# EEZ_DIB_AFE3_r1B1.net
KiCad netlist of a schematic drawn in EAGLE
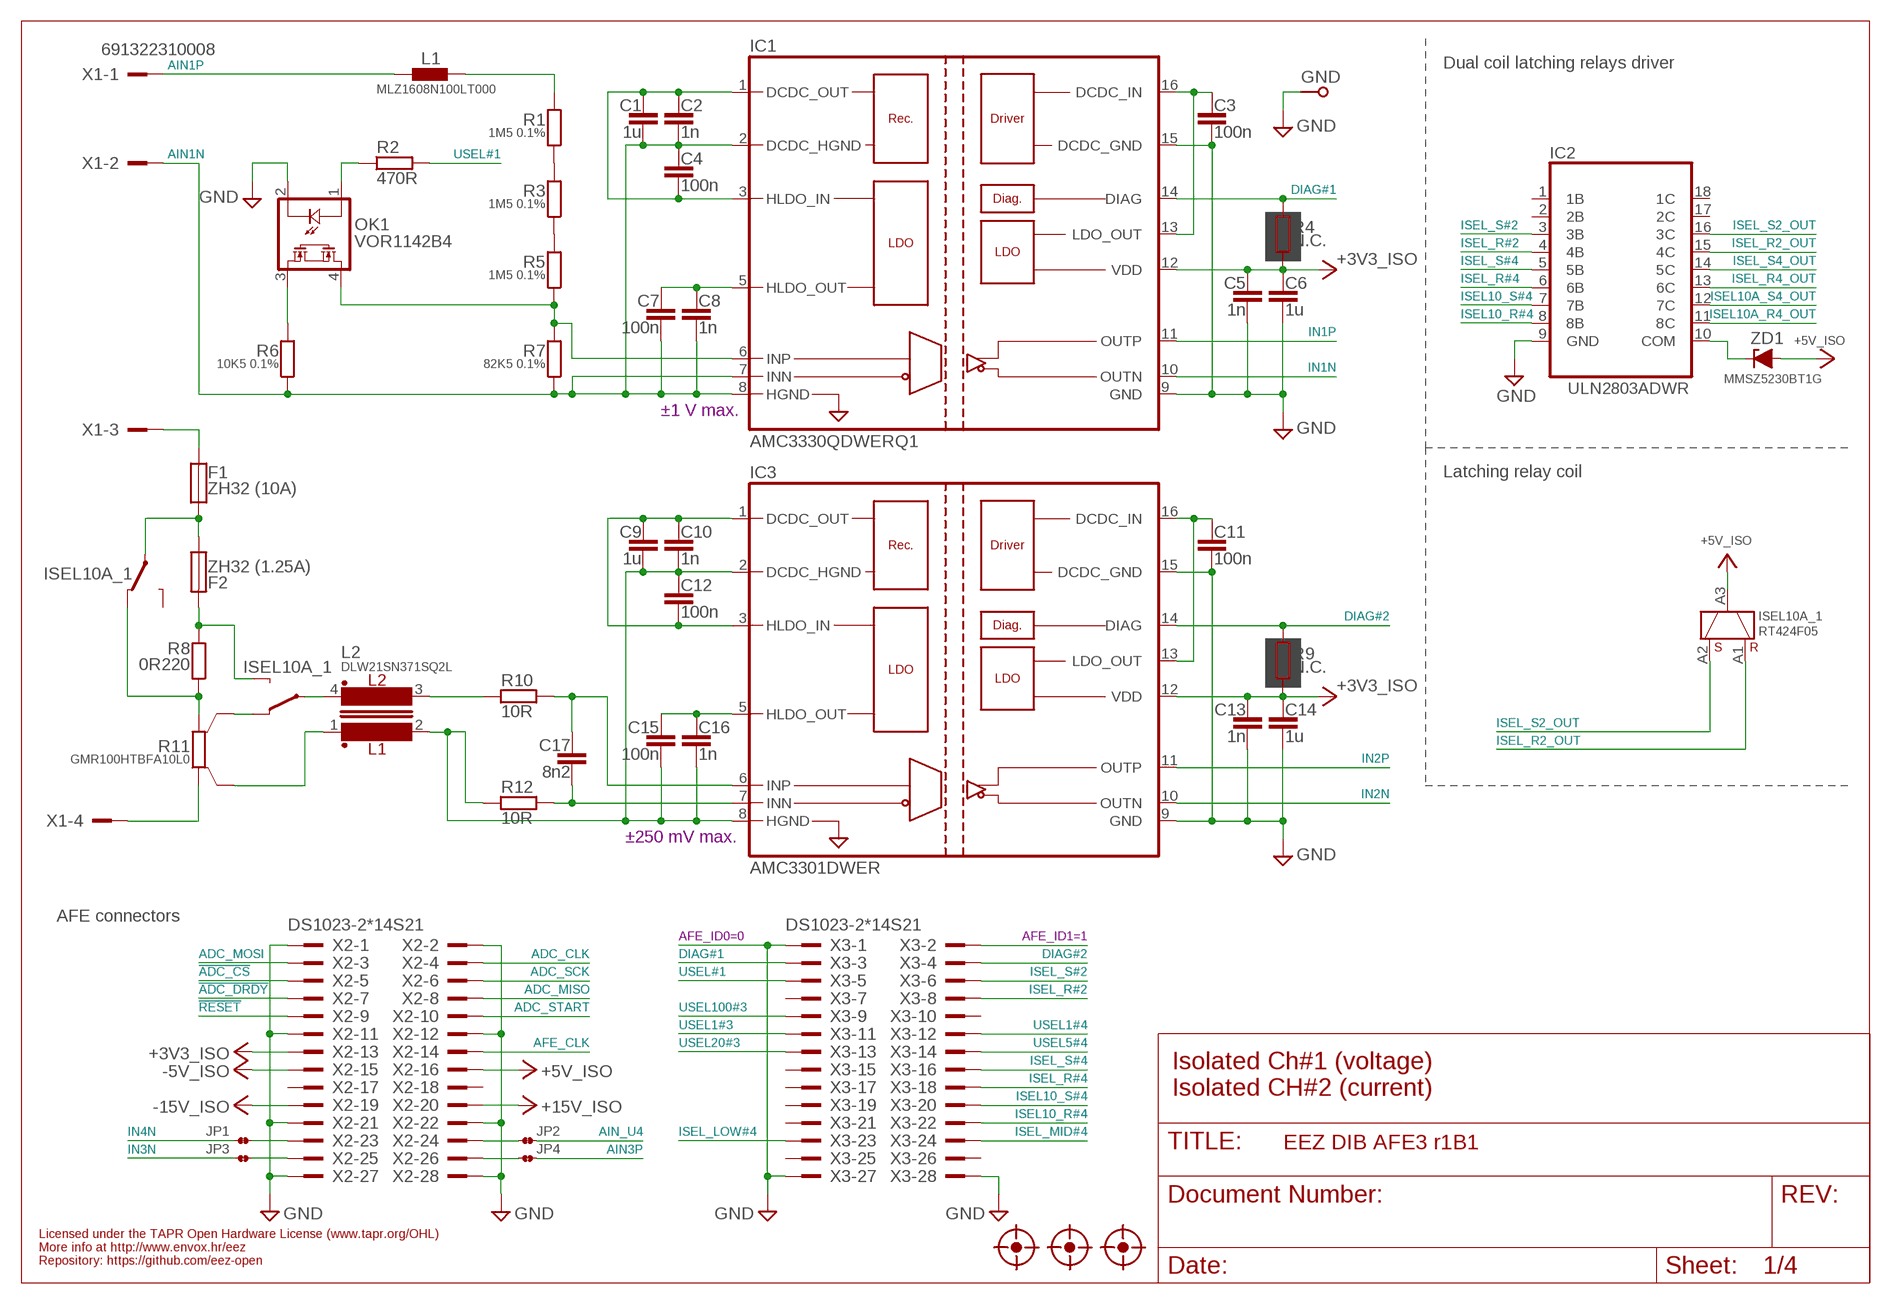
[diagram p0: schematic, sheet 1]
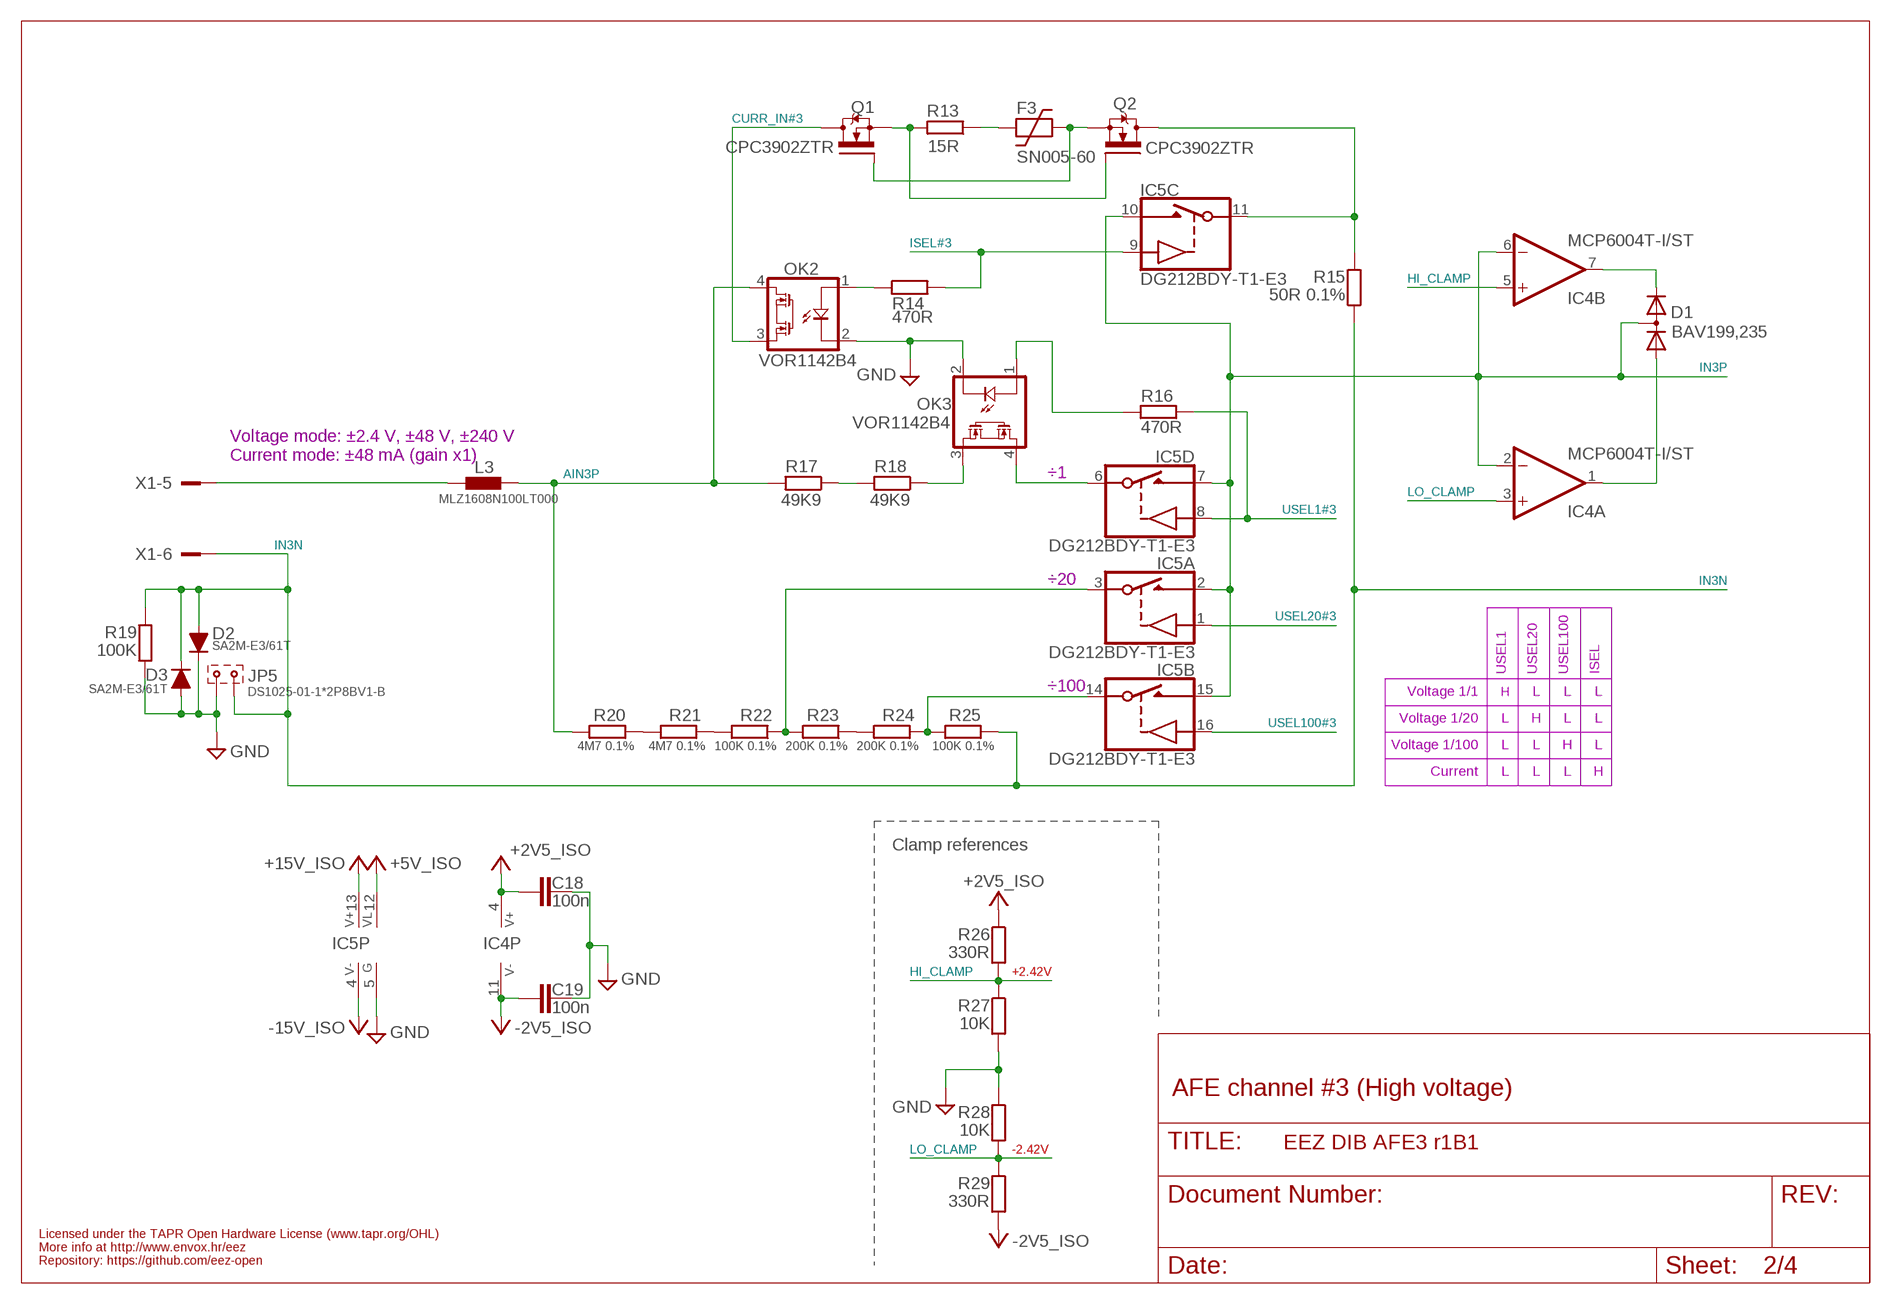
[diagram p1: schematic, sheet 2]
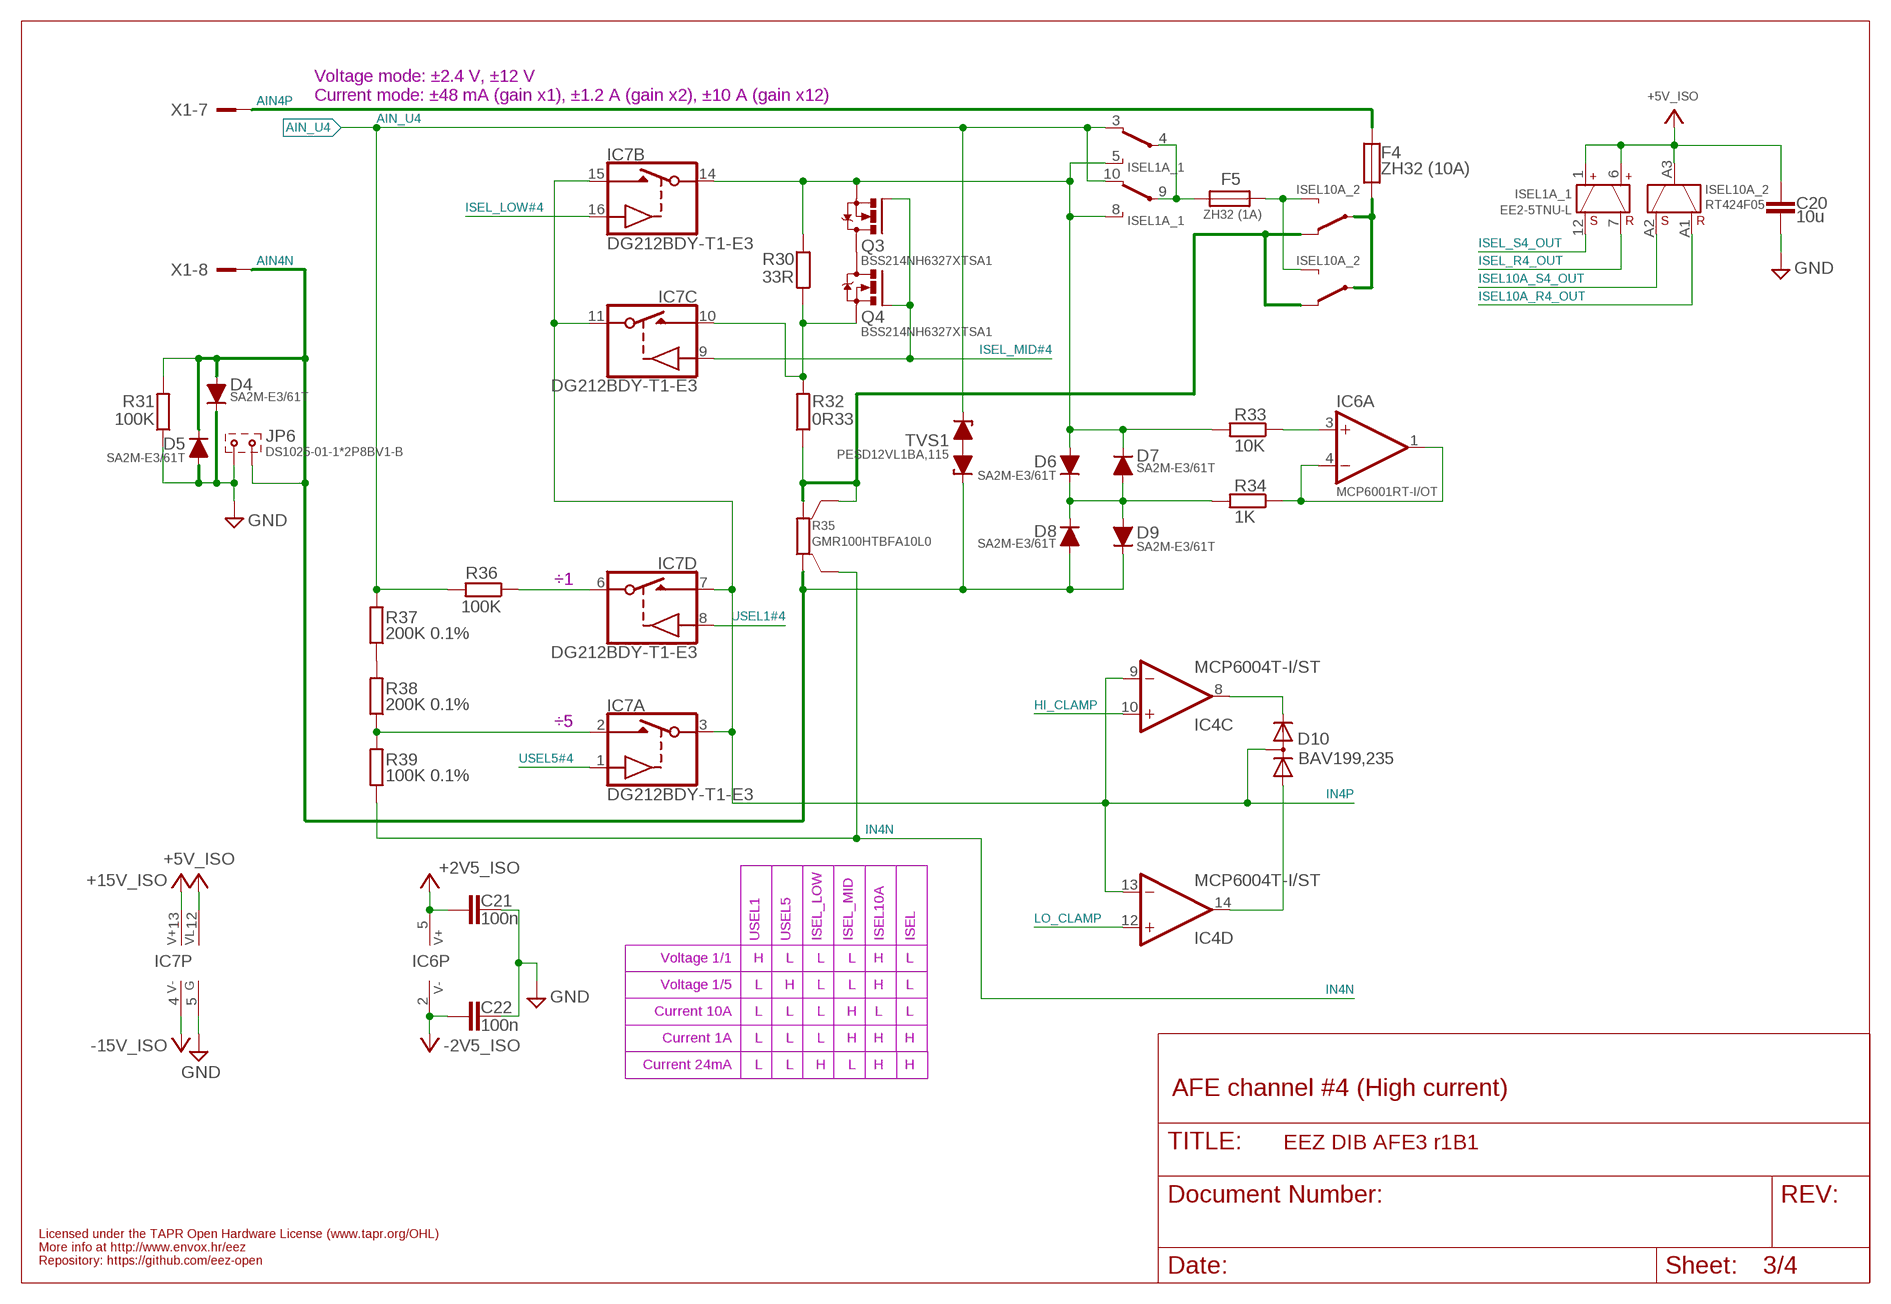
[diagram p2: schematic, sheet 3]
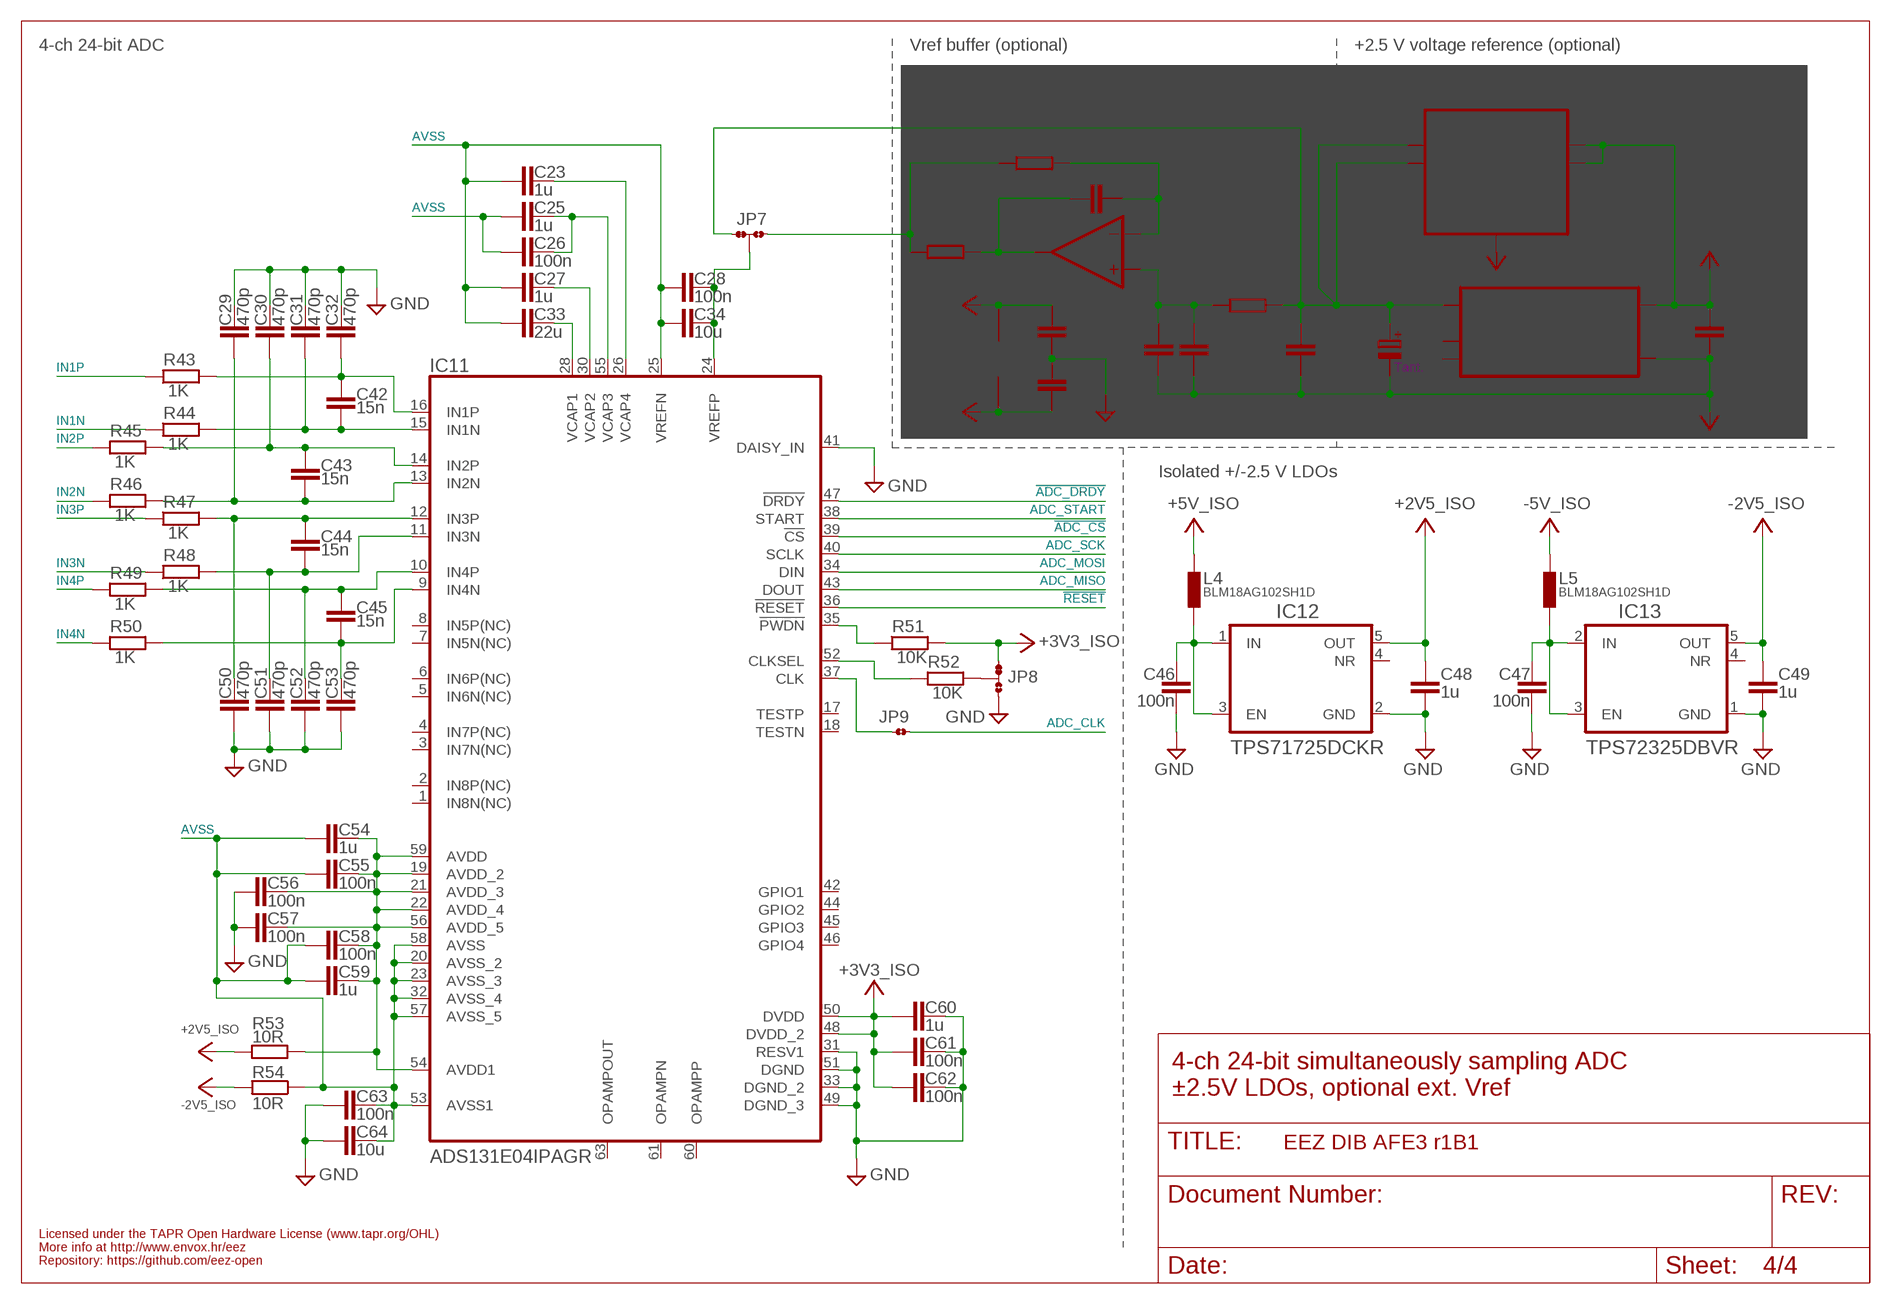
[diagram p3: schematic, sheet 4]

(export (version "E")
  (design (tool "Eeschema 10.0.6"))
  (components
    (comp (ref "C20")
      (value "10u")
      (footprint "eagle-import:C1206")
      (libsource (lib "eagle-import") (part "C-EUC1206"))
    )
    (comp (ref "C21")
      (value "100n")
      (footprint "eagle-import:C0603")
      (libsource (lib "eagle-import") (part "C-EUC0603"))
    )
    (comp (ref "C22")
      (value "100n")
      (footprint "eagle-import:C0603")
      (libsource (lib "eagle-import") (part "C-EUC0603"))
    )
    (comp (ref "D4")
      (value "SA2M-E3/61T")
      (footprint "eagle-import:SMA_NARROW")
      (libsource (lib "eagle-import") (part "DIODE_SMA-NARROW"))
    )
    (comp (ref "D5")
      (value "SA2M-E3/61T")
      (footprint "eagle-import:SMA_NARROW")
      (libsource (lib "eagle-import") (part "DIODE_SMA-NARROW"))
    )
    (comp (ref "D6")
      (value "SA2M-E3/61T")
      (footprint "eagle-import:SMA_NARROW")
      (libsource (lib "eagle-import") (part "DIODE_SMA-NARROW"))
    )
    (comp (ref "D7")
      (value "SA2M-E3/61T")
      (footprint "eagle-import:SMA_NARROW")
      (libsource (lib "eagle-import") (part "DIODE_SMA-NARROW"))
    )
    (comp (ref "D8")
      (value "SA2M-E3/61T")
      (footprint "eagle-import:SMA_NARROW")
      (libsource (lib "eagle-import") (part "DIODE_SMA-NARROW"))
    )
    (comp (ref "D9")
      (value "SA2M-E3/61T")
      (footprint "eagle-import:SMA_NARROW")
      (libsource (lib "eagle-import") (part "DIODE_SMA-NARROW"))
    )
    (comp (ref "D10")
      (value "BAV199,235")
      (footprint "eagle-import:SOT23")
      (libsource (lib "eagle-import") (part "BAV199"))
    )
    (comp (ref "F4")
      (value "ZH32 (10A)")
      (footprint "eagle-import:ZH32")
      (libsource (lib "eagle-import") (part "ZH32"))
    )
    (comp (ref "F5")
      (value "ZH32 (1A)")
      (footprint "eagle-import:ZH32")
      (libsource (lib "eagle-import") (part "ZH32"))
    )
    (comp (ref "IC4")
      (value "MCP6004T-I/ST")
      (footprint "eagle-import:PW(R-PDSO-G14)")
      (libsource (lib "eagle-import") (part "OPA4197PW"))
    )
    (comp (ref "IC6")
      (value "MCP6001RT-I/OT")
      (footprint "eagle-import:DBV5")
      (libsource (lib "eagle-import") (part "OPA376AIDBVR"))
    )
    (comp (ref "IC7")
      (value "DG212BDY-T1-E3")
      (footprint "eagle-import:SO16")
      (libsource (lib "eagle-import") (part "DG212BDY-T1-E3"))
    )
    (comp (ref "ISEL1A_1")
      (value "EE2-5TNU-L")
      (footprint "eagle-import:G6SK-2F")
      (libsource (lib "eagle-import") (part "G6SK-2F"))
    )
    (comp (ref "ISEL10A_2")
      (value "RT424F05")
      (footprint "eagle-import:RT424FXX")
      (libsource (lib "eagle-import") (part "RT424FXX"))
    )
    (comp (ref "JP6")
      (value "DS1025-01-1*2P8BV1-B")
      (footprint "eagle-import:2MM-2")
      (libsource (lib "eagle-import") (part "JUMPER-2PIN-2MM"))
    )
    (comp (ref "Q3")
      (value "BSS214NH6327XTSA1")
      (footprint "eagle-import:SOT103P240X110-3N")
      (fields
        (field (name "MPN") "2N7002-7-F")
        (field (name "MPN_1") "2N7002-7-F")
        (field (name "OC_FARNELL") "1713823")
        (field (name "OC_NEWARK") "25R5679")
        (field (name "PACKAGE") "SOT-23-3")
        (field (name "SUPPLIER") "DIODES INC.")
      )
      (libsource (lib "eagle-import") (part "2N7002"))
    )
    (comp (ref "Q4")
      (value "BSS214NH6327XTSA1")
      (footprint "eagle-import:SOT103P240X110-3N")
      (fields (field (name "MPN") "2N7002-7-F"))
      (libsource (lib "eagle-import") (part "2N7002"))
    )
    (comp (ref "R30")
      (value "33R")
      (footprint "eagle-import:R1206")
      (libsource (lib "eagle-import") (part "R-EU_R1206"))
    )
    (comp (ref "R31")
      (value "100K")
      (footprint "eagle-import:R1206")
      (libsource (lib "eagle-import") (part "R-EU_R1206"))
    )
    (comp (ref "R32")
      (value "0R33")
      (footprint "eagle-import:R1210")
      (libsource (lib "eagle-import") (part "R-EU_R1210"))
    )
    (comp (ref "R33")
      (value "10K")
      (footprint "eagle-import:R0805")
      (libsource (lib "eagle-import") (part "R-EU_R0805"))
    )
    (comp (ref "R34")
      (value "1K")
      (footprint "eagle-import:R0805")
      (libsource (lib "eagle-import") (part "R-EU_R0805"))
    )
    (comp (ref "R35")
      (value "GMR100HTBFA10L0")
      (footprint "eagle-import:R_2512-4WIRE")
      (libsource (lib "eagle-import") (part "R-EU_4WIRE2512"))
    )
    (comp (ref "R36")
      (value "100K")
      (footprint "eagle-import:R1206")
      (libsource (lib "eagle-import") (part "R-EU_R1206"))
    )
    (comp (ref "R37")
      (value "200K 0.1%")
      (footprint "eagle-import:R1206")
      (libsource (lib "eagle-import") (part "R-EU_R1206"))
    )
    (comp (ref "R38")
      (value "200K 0.1%")
      (footprint "eagle-import:R1206")
      (libsource (lib "eagle-import") (part "R-EU_R1206"))
    )
    (comp (ref "R39")
      (value "100K 0.1%")
      (footprint "eagle-import:R1206")
      (libsource (lib "eagle-import") (part "R-EU_R1206"))
    )
    (comp (ref "TVS1")
      (value "PESD12VL1BA,115")
      (footprint "eagle-import:SOD323-BIDIR")
      (libsource (lib "eagle-import") (part "PESDXL1BA"))
    )
    (comp (ref "X1")
      (value "691322310008")
      (footprint "eagle-import:691322310008")
      (libsource (lib "eagle-import") (part "691322310008"))
    )
    (comp (ref "C1")
      (value "1u")
      (footprint "eagle-import:C0603")
      (libsource (lib "eagle-import") (part "C-EUC0603"))
    )
    (comp (ref "C2")
      (value "1n")
      (footprint "eagle-import:C0603")
      (libsource (lib "eagle-import") (part "C-EUC0603"))
    )
    (comp (ref "C3")
      (value "100n")
      (footprint "eagle-import:C0603")
      (libsource (lib "eagle-import") (part "C-EUC0603"))
    )
    (comp (ref "C4")
      (value "100n")
      (footprint "eagle-import:C0603")
      (libsource (lib "eagle-import") (part "C-EUC0603"))
    )
    (comp (ref "C5")
      (value "1n")
      (footprint "eagle-import:C1206")
      (libsource (lib "eagle-import") (part "C-EUC1206"))
    )
    (comp (ref "C6")
      (value "1u")
      (footprint "eagle-import:C1206")
      (libsource (lib "eagle-import") (part "C-EUC1206"))
    )
    (comp (ref "C7")
      (value "100n")
      (footprint "eagle-import:C1206")
      (libsource (lib "eagle-import") (part "C-EUC1206"))
    )
    (comp (ref "C8")
      (value "1n")
      (footprint "eagle-import:C1206")
      (libsource (lib "eagle-import") (part "C-EUC1206"))
    )
    (comp (ref "C9")
      (value "1u")
      (footprint "eagle-import:C0603")
      (libsource (lib "eagle-import") (part "C-EUC0603"))
    )
    (comp (ref "C10")
      (value "1n")
      (footprint "eagle-import:C0603")
      (libsource (lib "eagle-import") (part "C-EUC0603"))
    )
    (comp (ref "C11")
      (value "100n")
      (footprint "eagle-import:C0603")
      (libsource (lib "eagle-import") (part "C-EUC0603"))
    )
    (comp (ref "C12")
      (value "100n")
      (footprint "eagle-import:C0603")
      (libsource (lib "eagle-import") (part "C-EUC0603"))
    )
    (comp (ref "C13")
      (value "1n")
      (footprint "eagle-import:C1206")
      (libsource (lib "eagle-import") (part "C-EUC1206"))
    )
    (comp (ref "C14")
      (value "1u")
      (footprint "eagle-import:C1206")
      (libsource (lib "eagle-import") (part "C-EUC1206"))
    )
    (comp (ref "C15")
      (value "100n")
      (footprint "eagle-import:C1206")
      (libsource (lib "eagle-import") (part "C-EUC1206"))
    )
    (comp (ref "C16")
      (value "1n")
      (footprint "eagle-import:C1206")
      (libsource (lib "eagle-import") (part "C-EUC1206"))
    )
    (comp (ref "C17")
      (value "8n2")
      (footprint "eagle-import:C0603")
      (libsource (lib "eagle-import") (part "C-EUC0603"))
    )
    (comp (ref "F1")
      (value "ZH32 (10A)")
      (footprint "eagle-import:ZH32")
      (libsource (lib "eagle-import") (part "ZH32"))
    )
    (comp (ref "F2")
      (value "ZH32 (1.25A)")
      (footprint "eagle-import:ZH32")
      (libsource (lib "eagle-import") (part "ZH32"))
    )
    (comp (ref "FM1")
      (value "FIDUCIAL_2")
      (footprint "eagle-import:FIDUCIAL_DUAL")
      (libsource (lib "eagle-import") (part "FIDUCIAL_2"))
    )
    (comp (ref "FM2")
      (value "FIDUCIAL_2")
      (footprint "eagle-import:FIDUCIAL_DUAL")
      (libsource (lib "eagle-import") (part "FIDUCIAL_2"))
    )
    (comp (ref "FM3")
      (value "FIDUCIAL_2")
      (footprint "eagle-import:FIDUCIAL_DUAL")
      (libsource (lib "eagle-import") (part "FIDUCIAL_2"))
    )
    (comp (ref "GND")
      (value "PCB_TEST_TABSHIELD")
      (footprint "eagle-import:PCB_SHIELD_TAB")
      (libsource (lib "eagle-import") (part "PCB_TEST_TABSHIELD"))
    )
    (comp (ref "IC1")
      (value "AMC3330QDWERQ1")
      (footprint "eagle-import:DW16")
      (libsource (lib "eagle-import") (part "AMC3301DWER"))
    )
    (comp (ref "IC2")
      (value "ULN2803ADWR")
      (footprint "eagle-import:DW18_TEX-M")
      (libsource (lib "eagle-import") (part "ULN2803ADWR"))
    )
    (comp (ref "IC3")
      (value "AMC3301DWER")
      (footprint "eagle-import:DW16")
      (libsource (lib "eagle-import") (part "AMC3301DWER"))
    )
    (comp (ref "ISEL10A_1")
      (value "RT424F05")
      (footprint "eagle-import:RT424FXX")
      (libsource (lib "eagle-import") (part "RT424FXX"))
    )
    (comp (ref "JP1")
      (value "JP2-NOCUT-0805")
      (footprint "eagle-import:JP2-0805-NOCUT")
      (libsource (lib "eagle-import") (part "JP2-NOCUT-0805"))
    )
    (comp (ref "JP2")
      (value "JP2-NOCUT-0805")
      (footprint "eagle-import:JP2-0805-NOCUT")
      (libsource (lib "eagle-import") (part "JP2-NOCUT-0805"))
    )
    (comp (ref "JP3")
      (value "JP2-NOCUT-0805")
      (footprint "eagle-import:JP2-0805-NOCUT")
      (libsource (lib "eagle-import") (part "JP2-NOCUT-0805"))
    )
    (comp (ref "JP4")
      (value "JP2-NOCUT-0805")
      (footprint "eagle-import:JP2-0805-NOCUT")
      (libsource (lib "eagle-import") (part "JP2-NOCUT-0805"))
    )
    (comp (ref "L1")
      (value "MLZ1608N100LT000")
      (footprint "eagle-import:BEAD0603")
      (libsource (lib "eagle-import") (part "FERRITE_BEAD0603"))
    )
    (comp (ref "L2")
      (value "DLW21SN371SQ2L")
      (footprint "eagle-import:MURATA_DLW21S")
      (libsource (lib "eagle-import") (part "DLW21S"))
    )
    (comp (ref "OK1")
      (value "VOR1142B4")
      (footprint "eagle-import:DIL4-SMD")
      (libsource (lib "eagle-import") (part "VOR1142B4"))
    )
    (comp (ref "R1")
      (value "1M5 0.1%")
      (footprint "eagle-import:R1206")
      (libsource (lib "eagle-import") (part "R-EU_R1206"))
    )
    (comp (ref "R2")
      (value "470R")
      (footprint "eagle-import:R0805")
      (libsource (lib "eagle-import") (part "R-EU_R0805"))
    )
    (comp (ref "R3")
      (value "1M5 0.1%")
      (footprint "eagle-import:R1206")
      (libsource (lib "eagle-import") (part "R-EU_R1206"))
    )
    (comp (ref "R4")
      (value "N.C.")
      (footprint "eagle-import:R0805")
      (libsource (lib "eagle-import") (part "R-EU_R0805"))
    )
    (comp (ref "R5")
      (value "1M5 0.1%")
      (footprint "eagle-import:R1206")
      (libsource (lib "eagle-import") (part "R-EU_R1206"))
    )
    (comp (ref "R6")
      (value "10K5 0.1%")
      (footprint "eagle-import:R1206")
      (libsource (lib "eagle-import") (part "R-EU_R1206"))
    )
    (comp (ref "R7")
      (value "82K5 0.1%")
      (footprint "eagle-import:R1206")
      (libsource (lib "eagle-import") (part "R-EU_R1206"))
    )
    (comp (ref "R8")
      (value "0R220")
      (footprint "eagle-import:R1210")
      (libsource (lib "eagle-import") (part "R-EU_R1210"))
    )
    (comp (ref "R9")
      (value "N.C.")
      (footprint "eagle-import:R0805")
      (libsource (lib "eagle-import") (part "R-EU_R0805"))
    )
    (comp (ref "R10")
      (value "10R")
      (footprint "eagle-import:R0805")
      (libsource (lib "eagle-import") (part "R-EU_R0805"))
    )
    (comp (ref "R11")
      (value "GMR100HTBFA10L0")
      (footprint "eagle-import:R_2512-4WIRE")
      (libsource (lib "eagle-import") (part "R-EU_4WIRE2512"))
    )
    (comp (ref "R12")
      (value "10R")
      (footprint "eagle-import:R0805")
      (libsource (lib "eagle-import") (part "R-EU_R0805"))
    )
    (comp (ref "X2")
      (value "DS1023-2*14S21")
      (footprint "eagle-import:TSW-114-07-F-D")
      (libsource (lib "eagle-import") (part "TSW-114-07-F-D"))
    )
    (comp (ref "X3")
      (value "DS1023-2*14S21")
      (footprint "eagle-import:TSW-114-07-F-D")
      (libsource (lib "eagle-import") (part "TSW-114-07-F-D"))
    )
    (comp (ref "ZD1")
      (value "MMSZ5230BT1G")
      (footprint "eagle-import:SOD123")
      (libsource (lib "eagle-import") (part "ZENER-DIODESOD123"))
    )
    (comp (ref "C23")
      (value "1u")
      (footprint "eagle-import:C0805")
      (libsource (lib "eagle-import") (part "C-EUC0805"))
    )
    (comp (ref "C24")
      (value "N.C.")
      (footprint "eagle-import:C0805")
      (libsource (lib "eagle-import") (part "C-EUC0805"))
    )
    (comp (ref "C25")
      (value "1u")
      (footprint "eagle-import:C0805")
      (libsource (lib "eagle-import") (part "C-EUC0805"))
    )
    (comp (ref "C26")
      (value "100n")
      (footprint "eagle-import:C0603")
      (libsource (lib "eagle-import") (part "C-EUC0603"))
    )
    (comp (ref "C27")
      (value "1u")
      (footprint "eagle-import:C0805")
      (libsource (lib "eagle-import") (part "C-EUC0805"))
    )
    (comp (ref "C28")
      (value "100n")
      (footprint "eagle-import:C0603")
      (libsource (lib "eagle-import") (part "C-EUC0603"))
    )
    (comp (ref "C29")
      (value "470p")
      (footprint "eagle-import:C0603")
      (libsource (lib "eagle-import") (part "C-EUC0603"))
    )
    (comp (ref "C30")
      (value "470p")
      (footprint "eagle-import:C0603")
      (libsource (lib "eagle-import") (part "C-EUC0603"))
    )
    (comp (ref "C31")
      (value "470p")
      (footprint "eagle-import:C0603")
      (libsource (lib "eagle-import") (part "C-EUC0603"))
    )
    (comp (ref "C32")
      (value "470p")
      (footprint "eagle-import:C0603")
      (libsource (lib "eagle-import") (part "C-EUC0603"))
    )
    (comp (ref "C33")
      (value "22u")
      (footprint "eagle-import:C1206")
      (libsource (lib "eagle-import") (part "C-EUC1206"))
    )
    (comp (ref "C34")
      (value "10u")
      (footprint "eagle-import:C1206")
      (libsource (lib "eagle-import") (part "C-EUC1206"))
    )
    (comp (ref "C35")
      (value "N.C.")
      (footprint "eagle-import:C0603")
      (libsource (lib "eagle-import") (part "C-EUC0603"))
    )
    (comp (ref "C36")
      (value "N.C.")
      (footprint "eagle-import:C1206")
      (libsource (lib "eagle-import") (part "C-EUC1206"))
    )
    (comp (ref "C37")
      (value "N.C.")
      (footprint "eagle-import:C1206")
      (libsource (lib "eagle-import") (part "C-EUC1206"))
    )
    (comp (ref "C38")
      (value "N.C.")
      (footprint "eagle-import:C1206")
      (libsource (lib "eagle-import") (part "C-EUC1206"))
    )
    (comp (ref "C39")
      (value "N.C.")
      (footprint "eagle-import:C1206")
      (libsource (lib "eagle-import") (part "C-EUC1206"))
    )
    (comp (ref "C40")
      (value "N.C.")
      (footprint "eagle-import:EC1206")
      (libsource (lib "eagle-import") (part "ECAP1206"))
    )
    (comp (ref "C41")
      (value "N.C.")
      (footprint "eagle-import:C0603")
      (libsource (lib "eagle-import") (part "C-EUC0603"))
    )
    (comp (ref "C42")
      (value "15n")
      (footprint "eagle-import:C0603")
      (libsource (lib "eagle-import") (part "C-EUC0603"))
    )
    (comp (ref "C43")
      (value "15n")
      (footprint "eagle-import:C0603")
      (libsource (lib "eagle-import") (part "C-EUC0603"))
    )
    (comp (ref "C44")
      (value "15n")
      (footprint "eagle-import:C0603")
      (libsource (lib "eagle-import") (part "C-EUC0603"))
    )
    (comp (ref "C45")
      (value "15n")
      (footprint "eagle-import:C0603")
      (libsource (lib "eagle-import") (part "C-EUC0603"))
    )
    (comp (ref "C46")
      (value "100n")
      (footprint "eagle-import:C0603")
      (libsource (lib "eagle-import") (part "C-EUC0603"))
    )
    (comp (ref "C47")
      (value "100n")
      (footprint "eagle-import:C0603")
      (libsource (lib "eagle-import") (part "C-EUC0603"))
    )
    (comp (ref "C48")
      (value "1u")
      (footprint "eagle-import:C0805")
      (libsource (lib "eagle-import") (part "C-EUC0805"))
    )
    (comp (ref "C49")
      (value "1u")
      (footprint "eagle-import:C0805")
      (libsource (lib "eagle-import") (part "C-EUC0805"))
    )
    (comp (ref "C50")
      (value "470p")
      (footprint "eagle-import:C0603")
      (libsource (lib "eagle-import") (part "C-EUC0603"))
    )
    (comp (ref "C51")
      (value "470p")
      (footprint "eagle-import:C0603")
      (libsource (lib "eagle-import") (part "C-EUC0603"))
    )
    (comp (ref "C52")
      (value "470p")
      (footprint "eagle-import:C0603")
      (libsource (lib "eagle-import") (part "C-EUC0603"))
    )
    (comp (ref "C53")
      (value "470p")
      (footprint "eagle-import:C0603")
      (libsource (lib "eagle-import") (part "C-EUC0603"))
    )
    (comp (ref "C54")
      (value "1u")
      (footprint "eagle-import:C0805")
      (libsource (lib "eagle-import") (part "C-EUC0805"))
    )
    (comp (ref "C55")
      (value "100n")
      (footprint "eagle-import:C0603")
      (libsource (lib "eagle-import") (part "C-EUC0603"))
    )
    (comp (ref "C56")
      (value "100n")
      (footprint "eagle-import:C0603")
      (libsource (lib "eagle-import") (part "C-EUC0603"))
    )
    (comp (ref "C57")
      (value "100n")
      (footprint "eagle-import:C0603")
      (libsource (lib "eagle-import") (part "C-EUC0603"))
    )
    (comp (ref "C58")
      (value "100n")
      (footprint "eagle-import:C0603")
      (libsource (lib "eagle-import") (part "C-EUC0603"))
    )
    (comp (ref "C59")
      (value "1u")
      (footprint "eagle-import:C0805")
      (libsource (lib "eagle-import") (part "C-EUC0805"))
    )
    (comp (ref "C60")
      (value "1u")
      (footprint "eagle-import:C0805")
      (libsource (lib "eagle-import") (part "C-EUC0805"))
    )
    (comp (ref "C61")
      (value "100n")
      (footprint "eagle-import:C0603")
      (libsource (lib "eagle-import") (part "C-EUC0603"))
    )
    (comp (ref "C62")
      (value "100n")
      (footprint "eagle-import:C0603")
      (libsource (lib "eagle-import") (part "C-EUC0603"))
    )
    (comp (ref "C63")
      (value "100n")
      (footprint "eagle-import:C0603")
      (libsource (lib "eagle-import") (part "C-EUC0603"))
    )
    (comp (ref "C64")
      (value "10u")
      (footprint "eagle-import:C1206")
      (libsource (lib "eagle-import") (part "C-EUC1206"))
    )
    (comp (ref "IC8")
      (value "N.C.")
      (footprint "eagle-import:MSOP-8_MS_LIT")
      (libsource (lib "eagle-import") (part "LTC6655BHMS8"))
    )
    (comp (ref "IC9")
      (value "N.C.")
      (footprint "eagle-import:DBV5")
      (libsource (lib "eagle-import") (part "OPA376AIDBVR"))
    )
    (comp (ref "IC10")
      (value "N.C.")
      (footprint "eagle-import:SOIC127P600X175-8N")
      (libsource (lib "eagle-import") (part "REF50XX"))
    )
    (comp (ref "IC11")
      (value "ADS131E04IPAGR")
      (footprint "eagle-import:PAG64")
      (libsource (lib "eagle-import") (part "ADS131E0XIPAG"))
    )
    (comp (ref "IC12")
      (value "TPS71725DCKR")
      (footprint "eagle-import:DCK5")
      (libsource (lib "eagle-import") (part "TPS71725DCKR"))
    )
    (comp (ref "IC13")
      (value "TPS72325DBVR")
      (footprint "eagle-import:DBV5")
      (libsource (lib "eagle-import") (part "TPS72325DBVR"))
    )
    (comp (ref "JP7")
      (value "JP3-CUT-0805-ROTATED")
      (footprint "eagle-import:JP3-0805-CUT2")
      (libsource (lib "eagle-import") (part "JP3-CUT-0805-ROTATED"))
    )
    (comp (ref "JP8")
      (value "JP3-CUT-0805-ROTATED")
      (footprint "eagle-import:JP3-0805-CUT2")
      (libsource (lib "eagle-import") (part "JP3-CUT-0805-ROTATED"))
    )
    (comp (ref "JP9")
      (value "JP2-CUT-0805")
      (footprint "eagle-import:R_0805")
      (libsource (lib "eagle-import") (part "JP2-CUT-0805"))
    )
    (comp (ref "L4")
      (value "BLM18AG102SH1D")
      (footprint "eagle-import:BEAD0603")
      (libsource (lib "eagle-import") (part "FERRITE_BEAD0603"))
    )
    (comp (ref "L5")
      (value "BLM18AG102SH1D")
      (footprint "eagle-import:BEAD0603")
      (libsource (lib "eagle-import") (part "FERRITE_BEAD0603"))
    )
    (comp (ref "R40")
      (value "N.C.")
      (footprint "eagle-import:R0805")
      (libsource (lib "eagle-import") (part "R-EU_R0805"))
    )
    (comp (ref "R41")
      (value "N.C.")
      (footprint "eagle-import:R0805")
      (libsource (lib "eagle-import") (part "R-EU_R0805"))
    )
    (comp (ref "R42")
      (value "N.C.")
      (footprint "eagle-import:R0805")
      (libsource (lib "eagle-import") (part "R-EU_R0805"))
    )
    (comp (ref "R43")
      (value "1K")
      (footprint "eagle-import:R0805")
      (libsource (lib "eagle-import") (part "R-EU_R0805"))
    )
    (comp (ref "R44")
      (value "1K")
      (footprint "eagle-import:R0805")
      (libsource (lib "eagle-import") (part "R-EU_R0805"))
    )
    (comp (ref "R45")
      (value "1K")
      (footprint "eagle-import:R0805")
      (libsource (lib "eagle-import") (part "R-EU_R0805"))
    )
    (comp (ref "R46")
      (value "1K")
      (footprint "eagle-import:R0805")
      (libsource (lib "eagle-import") (part "R-EU_R0805"))
    )
    (comp (ref "R47")
      (value "1K")
      (footprint "eagle-import:R0805")
      (libsource (lib "eagle-import") (part "R-EU_R0805"))
    )
    (comp (ref "R48")
      (value "1K")
      (footprint "eagle-import:R0805")
      (libsource (lib "eagle-import") (part "R-EU_R0805"))
    )
    (comp (ref "R49")
      (value "1K")
      (footprint "eagle-import:R0805")
      (libsource (lib "eagle-import") (part "R-EU_R0805"))
    )
    (comp (ref "R50")
      (value "1K")
      (footprint "eagle-import:R0805")
      (libsource (lib "eagle-import") (part "R-EU_R0805"))
    )
    (comp (ref "R51")
      (value "10K")
      (footprint "eagle-import:R0805")
      (libsource (lib "eagle-import") (part "R-EU_R0805"))
    )
    (comp (ref "R52")
      (value "10K")
      (footprint "eagle-import:R0805")
      (libsource (lib "eagle-import") (part "R-EU_R0805"))
    )
    (comp (ref "R53")
      (value "10R")
      (footprint "eagle-import:R0805")
      (libsource (lib "eagle-import") (part "R-EU_R0805"))
    )
    (comp (ref "R54")
      (value "10R")
      (footprint "eagle-import:R0805")
      (libsource (lib "eagle-import") (part "R-EU_R0805"))
    )
    (comp (ref "C18")
      (value "100n")
      (footprint "eagle-import:C0603")
      (libsource (lib "eagle-import") (part "C-EUC0603"))
    )
    (comp (ref "C19")
      (value "100n")
      (footprint "eagle-import:C0603")
      (libsource (lib "eagle-import") (part "C-EUC0603"))
    )
    (comp (ref "D1")
      (value "BAV199,235")
      (footprint "eagle-import:SOT23")
      (libsource (lib "eagle-import") (part "BAV199"))
    )
    (comp (ref "D2")
      (value "SA2M-E3/61T")
      (footprint "eagle-import:SMA_NARROW")
      (libsource (lib "eagle-import") (part "DIODE_SMA-NARROW"))
    )
    (comp (ref "D3")
      (value "SA2M-E3/61T")
      (footprint "eagle-import:SMA_NARROW")
      (libsource (lib "eagle-import") (part "DIODE_SMA-NARROW"))
    )
    (comp (ref "F3")
      (value "SN005-60")
      (footprint "eagle-import:C1206-HV")
      (libsource (lib "eagle-import") (part "FUSE_RESETTABLE2"))
    )
    (comp (ref "IC5")
      (value "DG212BDY-T1-E3")
      (footprint "eagle-import:SO16")
      (libsource (lib "eagle-import") (part "DG212BDY-T1-E3"))
    )
    (comp (ref "JP5")
      (value "DS1025-01-1*2P8BV1-B")
      (footprint "eagle-import:2MM-2")
      (libsource (lib "eagle-import") (part "JUMPER-2PIN-2MM"))
    )
    (comp (ref "L3")
      (value "MLZ1608N100LT000")
      (footprint "eagle-import:BEAD0603")
      (libsource (lib "eagle-import") (part "FERRITE_BEAD0603"))
    )
    (comp (ref "OK2")
      (value "VOR1142B4")
      (footprint "eagle-import:DIL4-SMD")
      (libsource (lib "eagle-import") (part "VOR1142B4"))
    )
    (comp (ref "OK3")
      (value "VOR1142B4")
      (footprint "eagle-import:DIL4-SMD")
      (libsource (lib "eagle-import") (part "VOR1142B4"))
    )
    (comp (ref "Q1")
      (value "CPC3902ZTR")
      (footprint "eagle-import:SOT230P700X180-4N")
      (libsource (lib "eagle-import") (part "BSP129SOT-223"))
    )
    (comp (ref "Q2")
      (value "CPC3902ZTR")
      (footprint "eagle-import:SOT230P700X180-4N")
      (libsource (lib "eagle-import") (part "BSP129SOT-223"))
    )
    (comp (ref "R13")
      (value "15R")
      (footprint "eagle-import:R0805")
      (libsource (lib "eagle-import") (part "R-EU_R0805"))
    )
    (comp (ref "R14")
      (value "470R")
      (footprint "eagle-import:R0805")
      (libsource (lib "eagle-import") (part "R-EU_R0805"))
    )
    (comp (ref "R15")
      (value "50R 0.1%")
      (footprint "eagle-import:R1206")
      (libsource (lib "eagle-import") (part "R-EU_R1206"))
    )
    (comp (ref "R16")
      (value "470R")
      (footprint "eagle-import:R0805")
      (libsource (lib "eagle-import") (part "R-EU_R0805"))
    )
    (comp (ref "R17")
      (value "49K9")
      (footprint "eagle-import:R1206")
      (libsource (lib "eagle-import") (part "R-EU_R1206"))
    )
    (comp (ref "R18")
      (value "49K9")
      (footprint "eagle-import:R1206")
      (libsource (lib "eagle-import") (part "R-EU_R1206"))
    )
    (comp (ref "R19")
      (value "100K")
      (footprint "eagle-import:R1206")
      (libsource (lib "eagle-import") (part "R-EU_R1206"))
    )
    (comp (ref "R20")
      (value "4M7 0.1%")
      (footprint "eagle-import:R1206")
      (libsource (lib "eagle-import") (part "R-EU_R1206"))
    )
    (comp (ref "R21")
      (value "4M7 0.1%")
      (footprint "eagle-import:R1206")
      (libsource (lib "eagle-import") (part "R-EU_R1206"))
    )
    (comp (ref "R22")
      (value "100K 0.1%")
      (footprint "eagle-import:R1206")
      (libsource (lib "eagle-import") (part "R-EU_R1206"))
    )
    (comp (ref "R23")
      (value "200K 0.1%")
      (footprint "eagle-import:R1206")
      (libsource (lib "eagle-import") (part "R-EU_R1206"))
    )
    (comp (ref "R24")
      (value "200K 0.1%")
      (footprint "eagle-import:R1206")
      (libsource (lib "eagle-import") (part "R-EU_R1206"))
    )
    (comp (ref "R25")
      (value "100K 0.1%")
      (footprint "eagle-import:R1206")
      (libsource (lib "eagle-import") (part "R-EU_R1206"))
    )
    (comp (ref "R26")
      (value "330R")
      (footprint "eagle-import:R0805")
      (libsource (lib "eagle-import") (part "R-EU_R0805"))
    )
    (comp (ref "R27")
      (value "10K")
      (footprint "eagle-import:R0805")
      (libsource (lib "eagle-import") (part "R-EU_R0805"))
    )
    (comp (ref "R28")
      (value "10K")
      (footprint "eagle-import:R0805")
      (libsource (lib "eagle-import") (part "R-EU_R0805"))
    )
    (comp (ref "R29")
      (value "330R")
      (footprint "eagle-import:R0805")
      (libsource (lib "eagle-import") (part "R-EU_R0805"))
    )
  )
  (nets
    (net (code "1") (name "+2V5_ISO") (class "Default")
      (node (ref "C18") (pin "2") (pinfunction "2_2") (pintype "passive"))
      (node (ref "C21") (pin "2") (pinfunction "2_2") (pintype "passive"))
      (node (ref "C48") (pin "2") (pinfunction "2_2") (pintype "passive"))
      (node (ref "IC12") (pin "5") (pinfunction "OUT_5") (pintype "passive"))
      (node (ref "IC4") (pin "4") (pinfunction "V+_4") (pintype "power_in"))
      (node (ref "IC6") (pin "5") (pinfunction "V+_5") (pintype "power_in"))
      (node (ref "R26") (pin "1") (pinfunction "1_1") (pintype "passive"))
      (node (ref "R53") (pin "1") (pinfunction "1_1") (pintype "passive"))
    )
    (net (code "2") (name "+3V3_ISO") (class "Default")
      (node (ref "C13") (pin "1") (pinfunction "1_1") (pintype "passive"))
      (node (ref "C14") (pin "1") (pinfunction "1_1") (pintype "passive"))
      (node (ref "C5") (pin "1") (pinfunction "1_1") (pintype "passive"))
      (node (ref "C6") (pin "1") (pinfunction "1_1") (pintype "passive"))
      (node (ref "C60") (pin "1") (pinfunction "1_1") (pintype "passive"))
      (node (ref "C61") (pin "2") (pinfunction "2_2") (pintype "passive"))
      (node (ref "C62") (pin "2") (pinfunction "2_2") (pintype "passive"))
      (node (ref "IC1") (pin "12") (pinfunction "VDD_12") (pintype "passive"))
      (node (ref "IC11") (pin "48") (pinfunction "DVDD_2_48") (pintype "power_in"))
      (node (ref "IC11") (pin "50") (pinfunction "DVDD_50") (pintype "power_in"))
      (node (ref "IC3") (pin "12") (pinfunction "VDD_12") (pintype "passive"))
      (node (ref "JP8") (pin "NC") (pinfunction "NC_NC") (pintype "passive"))
      (node (ref "R4") (pin "2") (pinfunction "2_2") (pintype "passive"))
      (node (ref "R51") (pin "2") (pinfunction "2_2") (pintype "passive"))
      (node (ref "R9") (pin "2") (pinfunction "2_2") (pintype "passive"))
      (node (ref "X2") (pin "13") (pinfunction "1_13") (pintype "passive"))
    )
    (net (code "3") (name "+5V_ISO") (class "Default")
      (node (ref "C20") (pin "1") (pinfunction "1_1") (pintype "passive"))
      (node (ref "C35") (pin "1") (pinfunction "1_1") (pintype "passive"))
      (node (ref "C36") (pin "1") (pinfunction "1_1") (pintype "passive"))
      (node (ref "IC10") (pin "2") (pinfunction "VIN_2") (pintype "passive"))
      (node (ref "IC5") (pin "12") (pinfunction "VL_12") (pintype "power_in"))
      (node (ref "IC7") (pin "12") (pinfunction "VL_12") (pintype "power_in"))
      (node (ref "IC8") (pin "1") (pinfunction "~{SHDN}_1") (pintype "input"))
      (node (ref "IC8") (pin "2") (pinfunction "VIN_2") (pintype "input"))
      (node (ref "IC9") (pin "5") (pinfunction "V+_5") (pintype "power_in"))
      (node (ref "ISEL10A_1") (pin "A3") (pinfunction "COM_A3") (pintype "passive"))
      (node (ref "ISEL10A_2") (pin "A3") (pinfunction "COM_A3") (pintype "passive"))
      (node (ref "ISEL1A_1") (pin "1") (pinfunction "S+_1") (pintype "passive"))
      (node (ref "ISEL1A_1") (pin "6") (pinfunction "R+_6") (pintype "passive"))
      (node (ref "L4") (pin "P$2") (pinfunction "2_P$2") (pintype "passive"))
      (node (ref "X2") (pin "16") (pinfunction "1_16") (pintype "passive"))
      (node (ref "ZD1") (pin "A") (pinfunction "A_A") (pintype "passive"))
    )
    (net (code "4") (name "+15V_ISO") (class "Default")
      (node (ref "IC5") (pin "13") (pinfunction "V+_13") (pintype "power_in"))
      (node (ref "IC7") (pin "13") (pinfunction "V+_13") (pintype "power_in"))
      (node (ref "X2") (pin "20") (pinfunction "1_20") (pintype "passive"))
    )
    (net (code "5") (name "-2V5_ISO") (class "Default")
      (node (ref "C19") (pin "2") (pinfunction "2_2") (pintype "passive"))
      (node (ref "C22") (pin "2") (pinfunction "2_2") (pintype "passive"))
      (node (ref "C36") (pin "2") (pinfunction "2_2") (pintype "passive"))
      (node (ref "C37") (pin "2") (pinfunction "2_2") (pintype "passive"))
      (node (ref "C38") (pin "2") (pinfunction "2_2") (pintype "passive"))
      (node (ref "C39") (pin "2") (pinfunction "2_2") (pintype "passive"))
      (node (ref "C40") (pin "-") (pinfunction "-_-") (pintype "passive"))
      (node (ref "C49") (pin "2") (pinfunction "2_2") (pintype "passive"))
      (node (ref "IC10") (pin "4") (pinfunction "GND_4") (pintype "passive"))
      (node (ref "IC13") (pin "5") (pinfunction "OUT_5") (pintype "passive"))
      (node (ref "IC4") (pin "11") (pinfunction "V-_11") (pintype "power_in"))
      (node (ref "IC6") (pin "2") (pinfunction "V-_2") (pintype "power_in"))
      (node (ref "IC8") (pin "3") (pinfunction "GND_3") (pintype "power_in"))
      (node (ref "IC8") (pin "4") (pinfunction "GND_4") (pintype "power_in"))
      (node (ref "IC8") (pin "5") (pinfunction "GND_5") (pintype "power_in"))
      (node (ref "IC8") (pin "8") (pinfunction "GND_8") (pintype "power_in"))
      (node (ref "R29") (pin "2") (pinfunction "2_2") (pintype "passive"))
      (node (ref "R54") (pin "2") (pinfunction "2_2") (pintype "passive"))
    )
    (net (code "6") (name "-5V_ISO") (class "Default")
      (node (ref "C41") (pin "2") (pinfunction "2_2") (pintype "passive"))
      (node (ref "IC9") (pin "2") (pinfunction "V-_2") (pintype "power_in"))
      (node (ref "L5") (pin "P$2") (pinfunction "2_P$2") (pintype "passive"))
      (node (ref "X2") (pin "15") (pinfunction "1_15") (pintype "passive"))
    )
    (net (code "7") (name "-15V_ISO") (class "Default")
      (node (ref "IC5") (pin "4") (pinfunction "V-_4") (pintype "power_in"))
      (node (ref "IC7") (pin "4") (pinfunction "V-_4") (pintype "power_in"))
      (node (ref "X2") (pin "19") (pinfunction "1_19") (pintype "passive"))
    )
    (net (code "8") (name "ADC_CLK") (class "Default")
      (node (ref "JP9") (pin "1") (pinfunction "1_1") (pintype "passive"))
      (node (ref "X2") (pin "4") (pinfunction "1_4") (pintype "passive"))
    )
    (net (code "9") (name "ADC_MISO") (class "Default")
      (node (ref "IC11") (pin "43") (pinfunction "DOUT_43") (pintype "output"))
      (node (ref "X2") (pin "8") (pinfunction "1_8") (pintype "passive"))
    )
    (net (code "10") (name "ADC_MOSI") (class "Default")
      (node (ref "IC11") (pin "34") (pinfunction "DIN_34") (pintype "input"))
      (node (ref "X2") (pin "3") (pinfunction "1_3") (pintype "passive"))
    )
    (net (code "11") (name "ADC_SCK") (class "Default")
      (node (ref "IC11") (pin "40") (pinfunction "SCLK_40") (pintype "input"))
      (node (ref "X2") (pin "6") (pinfunction "1_6") (pintype "passive"))
    )
    (net (code "12") (name "ADC_START") (class "Default")
      (node (ref "IC11") (pin "38") (pinfunction "START_38") (pintype "input"))
      (node (ref "X2") (pin "10") (pinfunction "1_10") (pintype "passive"))
    )
    (net (code "13") (name "AFE_CLK") (class "Default")
      (node (ref "X2") (pin "14") (pinfunction "1_14") (pintype "passive"))
    )
    (net (code "14") (name "AIN1N") (class "Default")
      (node (ref "C1") (pin "2") (pinfunction "2_2") (pintype "passive"))
      (node (ref "C2") (pin "2") (pinfunction "2_2") (pintype "passive"))
      (node (ref "C4") (pin "1") (pinfunction "1_1") (pintype "passive"))
      (node (ref "C7") (pin "2") (pinfunction "2_2") (pintype "passive"))
      (node (ref "C8") (pin "2") (pinfunction "2_2") (pintype "passive"))
      (node (ref "IC1") (pin "2") (pinfunction "DCDC_HGND_2") (pintype "passive"))
      (node (ref "IC1") (pin "7") (pinfunction "INN_7") (pintype "input"))
      (node (ref "IC1") (pin "8") (pinfunction "HGND_8") (pintype "passive"))
      (node (ref "R6") (pin "1") (pinfunction "1_1") (pintype "passive"))
      (node (ref "R7") (pin "1") (pinfunction "1_1") (pintype "passive"))
      (node (ref "X1") (pin "2") (pinfunction "1_2") (pintype "passive"))
    )
    (net (code "15") (name "AIN1P") (class "Default")
      (node (ref "L1") (pin "P$2") (pinfunction "2_P$2") (pintype "passive"))
      (node (ref "X1") (pin "1") (pinfunction "1_1") (pintype "passive"))
    )
    (net (code "16") (name "AIN3P") (class "Default")
      (node (ref "JP4") (pin "2") (pinfunction "2_2") (pintype "passive"))
      (node (ref "L3") (pin "P$1") (pinfunction "1_P$1") (pintype "passive"))
      (node (ref "OK2") (pin "4") (pinfunction "S1_4") (pintype "passive"))
      (node (ref "R17") (pin "2") (pinfunction "2_2") (pintype "passive"))
      (node (ref "R20") (pin "2") (pinfunction "2_2") (pintype "passive"))
    )
    (net (code "17") (name "AIN4N") (class "Default")
      (node (ref "D4") (pin "2") (pinfunction "A_2") (pintype "passive"))
      (node (ref "D5") (pin "1") (pinfunction "C_1") (pintype "passive"))
      (node (ref "D8") (pin "2") (pinfunction "A_2") (pintype "passive"))
      (node (ref "D9") (pin "1") (pinfunction "C_1") (pintype "passive"))
      (node (ref "JP6") (pin "1") (pinfunction "1_1") (pintype "passive"))
      (node (ref "R31") (pin "2") (pinfunction "2_2") (pintype "passive"))
      (node (ref "R35") (pin "1") (pinfunction "1_1") (pintype "passive"))
      (node (ref "TVS1") (pin "C1") (pinfunction "1_C1") (pintype "passive"))
      (node (ref "X1") (pin "8") (pinfunction "1_8") (pintype "passive"))
    )
    (net (code "18") (name "AIN4P") (class "Default")
      (node (ref "F4") (pin "2") (pinfunction "2_2") (pintype "passive"))
      (node (ref "X1") (pin "7") (pinfunction "1_7") (pintype "passive"))
    )
    (net (code "19") (name "AIN_U4") (class "Default")
      (node (ref "ISEL1A_1") (pin "10") (pinfunction "NC_10") (pintype "passive"))
      (node (ref "ISEL1A_1") (pin "3") (pinfunction "NC_3") (pintype "passive"))
      (node (ref "JP2") (pin "2") (pinfunction "2_2") (pintype "passive"))
      (node (ref "R36") (pin "2") (pinfunction "2_2") (pintype "passive"))
      (node (ref "R37") (pin "2") (pinfunction "2_2") (pintype "passive"))
      (node (ref "TVS1") (pin "C2") (pinfunction "2_C2") (pintype "passive"))
    )
    (net (code "20") (name "AVSS") (class "Default")
      (node (ref "C23") (pin "1") (pinfunction "1_1") (pintype "passive"))
      (node (ref "C25") (pin "1") (pinfunction "1_1") (pintype "passive"))
      (node (ref "C26") (pin "2") (pinfunction "2_2") (pintype "passive"))
      (node (ref "C27") (pin "1") (pinfunction "1_1") (pintype "passive"))
      (node (ref "C28") (pin "2") (pinfunction "2_2") (pintype "passive"))
      (node (ref "C33") (pin "1") (pinfunction "1_1") (pintype "passive"))
      (node (ref "C34") (pin "2") (pinfunction "2_2") (pintype "passive"))
      (node (ref "C54") (pin "1") (pinfunction "1_1") (pintype "passive"))
      (node (ref "C55") (pin "2") (pinfunction "2_2") (pintype "passive"))
      (node (ref "C58") (pin "2") (pinfunction "2_2") (pintype "passive"))
      (node (ref "C59") (pin "1") (pinfunction "1_1") (pintype "passive"))
      (node (ref "C63") (pin "1") (pinfunction "1_1") (pintype "passive"))
      (node (ref "C64") (pin "1") (pinfunction "1_1") (pintype "passive"))
      (node (ref "IC11") (pin "20") (pinfunction "AVSS_2_20") (pintype "power_in"))
      (node (ref "IC11") (pin "23") (pinfunction "AVSS_3_23") (pintype "power_in"))
      (node (ref "IC11") (pin "25") (pinfunction "VREFN_25") (pintype "input"))
      (node (ref "IC11") (pin "32") (pinfunction "AVSS_4_32") (pintype "power_in"))
      (node (ref "IC11") (pin "53") (pinfunction "AVSS1_53") (pintype "power_in"))
      (node (ref "IC11") (pin "57") (pinfunction "AVSS_5_57") (pintype "power_in"))
      (node (ref "IC11") (pin "58") (pinfunction "AVSS_58") (pintype "power_in"))
      (node (ref "R54") (pin "1") (pinfunction "1_1") (pintype "passive"))
    )
    (net (code "21") (name "CURR_IN#3") (class "Default")
      (node (ref "OK2") (pin "3") (pinfunction "S2_3") (pintype "passive"))
      (node (ref "Q1") (pin "2") (pinfunction "D_2") (pintype "passive"))
      (node (ref "Q1") (pin "4") (pinfunction "D_4") (pintype "passive"))
    )
    (net (code "22") (name "DIAG#1") (class "Default")
      (node (ref "IC1") (pin "14") (pinfunction "DIAG_14") (pintype "output"))
      (node (ref "R4") (pin "1") (pinfunction "1_1") (pintype "passive"))
      (node (ref "X3") (pin "3") (pinfunction "1_3") (pintype "passive"))
    )
    (net (code "23") (name "DIAG#2") (class "Default")
      (node (ref "IC3") (pin "14") (pinfunction "DIAG_14") (pintype "output"))
      (node (ref "R9") (pin "1") (pinfunction "1_1") (pintype "passive"))
      (node (ref "X3") (pin "4") (pinfunction "1_4") (pintype "passive"))
    )
    (net (code "24") (name "GND") (class "Default")
      (node (ref "C11") (pin "2") (pinfunction "2_2") (pintype "passive"))
      (node (ref "C13") (pin "2") (pinfunction "2_2") (pintype "passive"))
      (node (ref "C14") (pin "2") (pinfunction "2_2") (pintype "passive"))
      (node (ref "C18") (pin "1") (pinfunction "1_1") (pintype "passive"))
      (node (ref "C19") (pin "1") (pinfunction "1_1") (pintype "passive"))
      (node (ref "C20") (pin "2") (pinfunction "2_2") (pintype "passive"))
      (node (ref "C21") (pin "1") (pinfunction "1_1") (pintype "passive"))
      (node (ref "C22") (pin "1") (pinfunction "1_1") (pintype "passive"))
      (node (ref "C29") (pin "1") (pinfunction "1_1") (pintype "passive"))
      (node (ref "C3") (pin "2") (pinfunction "2_2") (pintype "passive"))
      (node (ref "C30") (pin "1") (pinfunction "1_1") (pintype "passive"))
      (node (ref "C31") (pin "1") (pinfunction "1_1") (pintype "passive"))
      (node (ref "C32") (pin "1") (pinfunction "1_1") (pintype "passive"))
      (node (ref "C35") (pin "2") (pinfunction "2_2") (pintype "passive"))
      (node (ref "C41") (pin "1") (pinfunction "1_1") (pintype "passive"))
      (node (ref "C46") (pin "2") (pinfunction "2_2") (pintype "passive"))
      (node (ref "C47") (pin "2") (pinfunction "2_2") (pintype "passive"))
      (node (ref "C48") (pin "1") (pinfunction "1_1") (pintype "passive"))
      (node (ref "C49") (pin "1") (pinfunction "1_1") (pintype "passive"))
      (node (ref "C5") (pin "2") (pinfunction "2_2") (pintype "passive"))
      (node (ref "C50") (pin "1") (pinfunction "1_1") (pintype "passive"))
      (node (ref "C51") (pin "1") (pinfunction "1_1") (pintype "passive"))
      (node (ref "C52") (pin "1") (pinfunction "1_1") (pintype "passive"))
      (node (ref "C53") (pin "1") (pinfunction "1_1") (pintype "passive"))
      (node (ref "C56") (pin "2") (pinfunction "2_2") (pintype "passive"))
      (node (ref "C57") (pin "2") (pinfunction "2_2") (pintype "passive"))
      (node (ref "C6") (pin "2") (pinfunction "2_2") (pintype "passive"))
      (node (ref "C60") (pin "2") (pinfunction "2_2") (pintype "passive"))
      (node (ref "C61") (pin "1") (pinfunction "1_1") (pintype "passive"))
      (node (ref "C62") (pin "1") (pinfunction "1_1") (pintype "passive"))
      (node (ref "C63") (pin "2") (pinfunction "2_2") (pintype "passive"))
      (node (ref "C64") (pin "2") (pinfunction "2_2") (pintype "passive"))
      (node (ref "D2") (pin "1") (pinfunction "C_1") (pintype "passive"))
      (node (ref "D3") (pin "2") (pinfunction "A_2") (pintype "passive"))
      (node (ref "D4") (pin "1") (pinfunction "C_1") (pintype "passive"))
      (node (ref "D5") (pin "2") (pinfunction "A_2") (pintype "passive"))
      (node (ref "GND") (pin "1") (pinfunction "P$1_1") (pintype "bidirectional"))
      (node (ref "IC1") (pin "15") (pinfunction "DCDC_GND_15") (pintype "passive"))
      (node (ref "IC1") (pin "9") (pinfunction "GND_9") (pintype "passive"))
      (node (ref "IC11") (pin "31") (pinfunction "RESV1_31") (pintype "input"))
      (node (ref "IC11") (pin "33") (pinfunction "DGND_2_33") (pintype "power_in"))
      (node (ref "IC11") (pin "41") (pinfunction "DAISY_IN_41") (pintype "input"))
      (node (ref "IC11") (pin "49") (pinfunction "DGND_3_49") (pintype "power_in"))
      (node (ref "IC11") (pin "51") (pinfunction "DGND_51") (pintype "power_in"))
      (node (ref "IC12") (pin "2") (pinfunction "GND_2") (pintype "passive"))
      (node (ref "IC13") (pin "1") (pinfunction "GND_1") (pintype "passive"))
      (node (ref "IC2") (pin "9") (pinfunction "GND_9") (pintype "input"))
      (node (ref "IC3") (pin "15") (pinfunction "DCDC_GND_15") (pintype "passive"))
      (node (ref "IC3") (pin "9") (pinfunction "GND_9") (pintype "passive"))
      (node (ref "IC5") (pin "5") (pinfunction "GND_5") (pintype "power_in"))
      (node (ref "IC7") (pin "5") (pinfunction "GND_5") (pintype "power_in"))
      (node (ref "JP5") (pin "2") (pinfunction "2_2") (pintype "passive"))
      (node (ref "JP6") (pin "2") (pinfunction "2_2") (pintype "passive"))
      (node (ref "JP8") (pin "NO") (pinfunction "NO_NO") (pintype "passive"))
      (node (ref "OK1") (pin "2") (pinfunction "C_2") (pintype "passive"))
      (node (ref "OK2") (pin "2") (pinfunction "C_2") (pintype "passive"))
      (node (ref "OK3") (pin "2") (pinfunction "C_2") (pintype "passive"))
      (node (ref "R19") (pin "1") (pinfunction "1_1") (pintype "passive"))
      (node (ref "R27") (pin "2") (pinfunction "2_2") (pintype "passive"))
      (node (ref "R28") (pin "1") (pinfunction "1_1") (pintype "passive"))
      (node (ref "R31") (pin "1") (pinfunction "1_1") (pintype "passive"))
      (node (ref "X2") (pin "1") (pinfunction "1_1") (pintype "passive"))
      (node (ref "X2") (pin "11") (pinfunction "1_11") (pintype "passive"))
      (node (ref "X2") (pin "12") (pinfunction "1_12") (pintype "passive"))
      (node (ref "X2") (pin "2") (pinfunction "1_2") (pintype "passive"))
      (node (ref "X2") (pin "21") (pinfunction "1_21") (pintype "passive"))
      (node (ref "X2") (pin "22") (pinfunction "1_22") (pintype "passive"))
      (node (ref "X2") (pin "27") (pinfunction "1_27") (pintype "passive"))
      (node (ref "X2") (pin "28") (pinfunction "1_28") (pintype "passive"))
      (node (ref "X3") (pin "1") (pinfunction "1_1") (pintype "passive"))
      (node (ref "X3") (pin "27") (pinfunction "1_27") (pintype "passive"))
      (node (ref "X3") (pin "28") (pinfunction "1_28") (pintype "passive"))
    )
    (net (code "25") (name "HI_CLAMP") (class "Default")
      (node (ref "IC4") (pin "10") (pinfunction "+IN_10") (pintype "input"))
      (node (ref "IC4") (pin "5") (pinfunction "+IN_5") (pintype "input"))
      (node (ref "R26") (pin "2") (pinfunction "2_2") (pintype "passive"))
      (node (ref "R27") (pin "1") (pinfunction "1_1") (pintype "passive"))
    )
    (net (code "26") (name "IN1N") (class "Default")
      (node (ref "IC1") (pin "10") (pinfunction "OUTN_10") (pintype "output"))
      (node (ref "R44") (pin "1") (pinfunction "1_1") (pintype "passive"))
    )
    (net (code "27") (name "IN1P") (class "Default")
      (node (ref "IC1") (pin "11") (pinfunction "OUTP_11") (pintype "output"))
      (node (ref "R43") (pin "1") (pinfunction "1_1") (pintype "passive"))
    )
    (net (code "28") (name "IN2N") (class "Default")
      (node (ref "IC3") (pin "10") (pinfunction "OUTN_10") (pintype "output"))
      (node (ref "R46") (pin "1") (pinfunction "1_1") (pintype "passive"))
    )
    (net (code "29") (name "IN2P") (class "Default")
      (node (ref "IC3") (pin "11") (pinfunction "OUTP_11") (pintype "output"))
      (node (ref "R45") (pin "1") (pinfunction "1_1") (pintype "passive"))
    )
    (net (code "30") (name "IN3N") (class "Default")
      (node (ref "D2") (pin "2") (pinfunction "A_2") (pintype "passive"))
      (node (ref "D3") (pin "1") (pinfunction "C_1") (pintype "passive"))
      (node (ref "JP3") (pin "1") (pinfunction "1_1") (pintype "passive"))
      (node (ref "JP5") (pin "1") (pinfunction "1_1") (pintype "passive"))
      (node (ref "R15") (pin "1") (pinfunction "1_1") (pintype "passive"))
      (node (ref "R19") (pin "2") (pinfunction "2_2") (pintype "passive"))
      (node (ref "R25") (pin "1") (pinfunction "1_1") (pintype "passive"))
      (node (ref "R48") (pin "1") (pinfunction "1_1") (pintype "passive"))
      (node (ref "X1") (pin "6") (pinfunction "1_6") (pintype "passive"))
    )
    (net (code "31") (name "IN3P") (class "Default")
      (node (ref "D1") (pin "3") (pinfunction "AC_3") (pintype "passive"))
      (node (ref "IC4") (pin "2") (pinfunction "-IN_2") (pintype "input"))
      (node (ref "IC4") (pin "6") (pinfunction "-IN_6") (pintype "input"))
      (node (ref "IC5") (pin "10") (pinfunction "D_10") (pintype "bidirectional"))
      (node (ref "IC5") (pin "15") (pinfunction "D_15") (pintype "bidirectional"))
      (node (ref "IC5") (pin "2") (pinfunction "D_2") (pintype "bidirectional"))
      (node (ref "IC5") (pin "7") (pinfunction "D_7") (pintype "bidirectional"))
      (node (ref "R47") (pin "1") (pinfunction "1_1") (pintype "passive"))
    )
    (net (code "32") (name "IN4N") (class "Default")
      (node (ref "JP1") (pin "1") (pinfunction "1_1") (pintype "passive"))
      (node (ref "R35") (pin "1S") (pinfunction "1S_1S") (pintype "passive"))
      (node (ref "R39") (pin "1") (pinfunction "1_1") (pintype "passive"))
      (node (ref "R50") (pin "1") (pinfunction "1_1") (pintype "passive"))
    )
    (net (code "33") (name "IN4P") (class "Default")
      (node (ref "D10") (pin "3") (pinfunction "AC_3") (pintype "passive"))
      (node (ref "IC4") (pin "13") (pinfunction "-IN_13") (pintype "input"))
      (node (ref "IC4") (pin "9") (pinfunction "-IN_9") (pintype "input"))
      (node (ref "IC7") (pin "11") (pinfunction "S_11") (pintype "bidirectional"))
      (node (ref "IC7") (pin "15") (pinfunction "D_15") (pintype "bidirectional"))
      (node (ref "IC7") (pin "3") (pinfunction "S_3") (pintype "bidirectional"))
      (node (ref "IC7") (pin "7") (pinfunction "D_7") (pintype "bidirectional"))
      (node (ref "R49") (pin "1") (pinfunction "1_1") (pintype "passive"))
    )
    (net (code "34") (name "ISEL#3") (class "Default")
      (node (ref "IC5") (pin "9") (pinfunction "IN_9") (pintype "input"))
      (node (ref "R14") (pin "2") (pinfunction "2_2") (pintype "passive"))
    )
    (net (code "35") (name "ISEL10A_R4_OUT") (class "Default")
      (node (ref "IC2") (pin "11") (pinfunction "8C_11") (pintype "output"))
      (node (ref "ISEL10A_2") (pin "A1") (pinfunction "R_A1") (pintype "passive"))
    )
    (net (code "36") (name "ISEL10A_S4_OUT") (class "Default")
      (node (ref "IC2") (pin "12") (pinfunction "7C_12") (pintype "output"))
      (node (ref "ISEL10A_2") (pin "A2") (pinfunction "S_A2") (pintype "passive"))
    )
    (net (code "37") (name "ISEL10_R#4") (class "Default")
      (node (ref "IC2") (pin "8") (pinfunction "8B_8") (pintype "input"))
      (node (ref "X3") (pin "22") (pinfunction "1_22") (pintype "passive"))
    )
    (net (code "38") (name "ISEL10_S#4") (class "Default")
      (node (ref "IC2") (pin "7") (pinfunction "7B_7") (pintype "input"))
      (node (ref "X3") (pin "20") (pinfunction "1_20") (pintype "passive"))
    )
    (net (code "39") (name "ISEL_LOW#4") (class "Default")
      (node (ref "IC7") (pin "16") (pinfunction "IN_16") (pintype "input"))
      (node (ref "X3") (pin "23") (pinfunction "1_23") (pintype "passive"))
    )
    (net (code "40") (name "ISEL_MID#4") (class "Default")
      (node (ref "IC7") (pin "9") (pinfunction "IN_9") (pintype "input"))
      (node (ref "Q3") (pin "1") (pinfunction "G_1") (pintype "passive"))
      (node (ref "Q4") (pin "1") (pinfunction "G_1") (pintype "passive"))
      (node (ref "X3") (pin "24") (pinfunction "1_24") (pintype "passive"))
    )
    (net (code "41") (name "ISEL_R#2") (class "Default")
      (node (ref "IC2") (pin "4") (pinfunction "4B_4") (pintype "input"))
      (node (ref "X3") (pin "8") (pinfunction "1_8") (pintype "passive"))
    )
    (net (code "42") (name "ISEL_R#4") (class "Default")
      (node (ref "IC2") (pin "6") (pinfunction "6B_6") (pintype "input"))
      (node (ref "X3") (pin "18") (pinfunction "1_18") (pintype "passive"))
    )
    (net (code "43") (name "ISEL_R2_OUT") (class "Default")
      (node (ref "IC2") (pin "15") (pinfunction "4C_15") (pintype "output"))
      (node (ref "ISEL10A_1") (pin "A1") (pinfunction "R_A1") (pintype "passive"))
    )
    (net (code "44") (name "ISEL_R4_OUT") (class "Default")
      (node (ref "IC2") (pin "13") (pinfunction "6C_13") (pintype "output"))
      (node (ref "ISEL1A_1") (pin "7") (pinfunction "R-_7") (pintype "passive"))
    )
    (net (code "45") (name "ISEL_S#2") (class "Default")
      (node (ref "IC2") (pin "3") (pinfunction "3B_3") (pintype "input"))
      (node (ref "X3") (pin "6") (pinfunction "1_6") (pintype "passive"))
    )
    (net (code "46") (name "ISEL_S#4") (class "Default")
      (node (ref "IC2") (pin "5") (pinfunction "5B_5") (pintype "input"))
      (node (ref "X3") (pin "16") (pinfunction "1_16") (pintype "passive"))
    )
    (net (code "47") (name "ISEL_S2_OUT") (class "Default")
      (node (ref "IC2") (pin "16") (pinfunction "3C_16") (pintype "output"))
      (node (ref "ISEL10A_1") (pin "A2") (pinfunction "S_A2") (pintype "passive"))
    )
    (net (code "48") (name "ISEL_S4_OUT") (class "Default")
      (node (ref "IC2") (pin "14") (pinfunction "5C_14") (pintype "output"))
      (node (ref "ISEL1A_1") (pin "12") (pinfunction "S-_12") (pintype "passive"))
    )
    (net (code "49") (name "LO_CLAMP") (class "Default")
      (node (ref "IC4") (pin "12") (pinfunction "+IN_12") (pintype "input"))
      (node (ref "IC4") (pin "3") (pinfunction "+IN_3") (pintype "input"))
      (node (ref "R28") (pin "2") (pinfunction "2_2") (pintype "passive"))
      (node (ref "R29") (pin "1") (pinfunction "1_1") (pintype "passive"))
    )
    (net (code "50") (name "Net-(D1-A)") (class "Default")
      (node (ref "D1") (pin "1") (pinfunction "A_1") (pintype "passive"))
      (node (ref "IC4") (pin "1") (pinfunction "OUT_1") (pintype "output"))
    )
    (net (code "51") (name "Net-(D1-C)") (class "Default")
      (node (ref "D1") (pin "2") (pinfunction "C_2") (pintype "passive"))
      (node (ref "IC4") (pin "7") (pinfunction "OUT_7") (pintype "output"))
    )
    (net (code "52") (name "Net-(D6-A)") (class "Default")
      (node (ref "D6") (pin "2") (pinfunction "A_2") (pintype "passive"))
      (node (ref "D7") (pin "1") (pinfunction "C_1") (pintype "passive"))
      (node (ref "IC7") (pin "14") (pinfunction "S_14") (pintype "bidirectional"))
      (node (ref "ISEL1A_1") (pin "5") (pinfunction "NO_5") (pintype "passive"))
      (node (ref "ISEL1A_1") (pin "8") (pinfunction "NO_8") (pintype "passive"))
      (node (ref "Q3") (pin "2") (pinfunction "S_2") (pintype "passive"))
      (node (ref "R30") (pin "2") (pinfunction "2_2") (pintype "passive"))
      (node (ref "R33") (pin "2") (pinfunction "2_2") (pintype "passive"))
    )
    (net (code "53") (name "Net-(D6-C)") (class "Default")
      (node (ref "D6") (pin "1") (pinfunction "C_1") (pintype "passive"))
      (node (ref "D7") (pin "2") (pinfunction "A_2") (pintype "passive"))
      (node (ref "D8") (pin "1") (pinfunction "C_1") (pintype "passive"))
      (node (ref "D9") (pin "2") (pinfunction "A_2") (pintype "passive"))
      (node (ref "R34") (pin "2") (pinfunction "2_2") (pintype "passive"))
    )
    (net (code "54") (name "Net-(D10-A)") (class "Default")
      (node (ref "D10") (pin "1") (pinfunction "A_1") (pintype "passive"))
      (node (ref "IC4") (pin "14") (pinfunction "OUT_14") (pintype "output"))
    )
    (net (code "55") (name "Net-(D10-C)") (class "Default")
      (node (ref "D10") (pin "2") (pinfunction "C_2") (pintype "passive"))
      (node (ref "IC4") (pin "8") (pinfunction "OUT_8") (pintype "output"))
    )
    (net (code "56") (name "Net-(F3-P$1)") (class "Default")
      (node (ref "F3") (pin "1") (pinfunction "P$1_1") (pintype "bidirectional"))
      (node (ref "R13") (pin "1") (pinfunction "1_1") (pintype "passive"))
    )
    (net (code "57") (name "Net-(F3-P$2)") (class "Default")
      (node (ref "F3") (pin "2") (pinfunction "P$2_2") (pintype "bidirectional"))
      (node (ref "Q1") (pin "1") (pinfunction "G_1") (pintype "passive"))
      (node (ref "Q2") (pin "3") (pinfunction "S_3") (pintype "passive"))
    )
    (net (code "58") (name "Net-(IC1-DCDC_IN)") (class "Default")
      (node (ref "C3") (pin "1") (pinfunction "1_1") (pintype "passive"))
      (node (ref "IC1") (pin "13") (pinfunction "LDO_OUT_13") (pintype "passive"))
      (node (ref "IC1") (pin "16") (pinfunction "DCDC_IN_16") (pintype "passive"))
    )
    (net (code "59") (name "Net-(IC1-DCDC_OUT)") (class "Default")
      (node (ref "C1") (pin "1") (pinfunction "1_1") (pintype "passive"))
      (node (ref "C2") (pin "1") (pinfunction "1_1") (pintype "passive"))
      (node (ref "C4") (pin "2") (pinfunction "2_2") (pintype "passive"))
      (node (ref "IC1") (pin "1") (pinfunction "DCDC_OUT_1") (pintype "passive"))
      (node (ref "IC1") (pin "3") (pinfunction "HLDO_IN_3") (pintype "passive"))
    )
    (net (code "60") (name "Net-(IC1-HLDO_OUT)") (class "Default")
      (node (ref "C7") (pin "1") (pinfunction "1_1") (pintype "passive"))
      (node (ref "C8") (pin "1") (pinfunction "1_1") (pintype "passive"))
      (node (ref "IC1") (pin "5") (pinfunction "HLDO_OUT_5") (pintype "passive"))
    )
    (net (code "61") (name "Net-(IC1-INP)") (class "Default")
      (node (ref "IC1") (pin "6") (pinfunction "INP_6") (pintype "input"))
      (node (ref "OK1") (pin "4") (pinfunction "S1_4") (pintype "passive"))
      (node (ref "R5") (pin "1") (pinfunction "1_1") (pintype "passive"))
      (node (ref "R7") (pin "2") (pinfunction "2_2") (pintype "passive"))
    )
    (net (code "62") (name "Net-(IC2-COM)") (class "Default")
      (node (ref "IC2") (pin "10") (pinfunction "COM_10") (pintype "passive"))
      (node (ref "ZD1") (pin "C") (pinfunction "C_C") (pintype "passive"))
    )
    (net (code "63") (name "Net-(IC3-DCDC_HGND)") (class "Default")
      (node (ref "C10") (pin "2") (pinfunction "2_2") (pintype "passive"))
      (node (ref "C12") (pin "1") (pinfunction "1_1") (pintype "passive"))
      (node (ref "C15") (pin "2") (pinfunction "2_2") (pintype "passive"))
      (node (ref "C16") (pin "2") (pinfunction "2_2") (pintype "passive"))
      (node (ref "C9") (pin "2") (pinfunction "2_2") (pintype "passive"))
      (node (ref "IC3") (pin "2") (pinfunction "DCDC_HGND_2") (pintype "passive"))
      (node (ref "IC3") (pin "8") (pinfunction "HGND_8") (pintype "passive"))
      (node (ref "L2") (pin "2") (pinfunction "2_2") (pintype "passive"))
      (node (ref "R12") (pin "2") (pinfunction "2_2") (pintype "passive"))
    )
    (net (code "64") (name "Net-(IC3-DCDC_IN)") (class "Default")
      (node (ref "C11") (pin "1") (pinfunction "1_1") (pintype "passive"))
      (node (ref "IC3") (pin "13") (pinfunction "LDO_OUT_13") (pintype "passive"))
      (node (ref "IC3") (pin "16") (pinfunction "DCDC_IN_16") (pintype "passive"))
    )
    (net (code "65") (name "Net-(IC3-DCDC_OUT)") (class "Default")
      (node (ref "C10") (pin "1") (pinfunction "1_1") (pintype "passive"))
      (node (ref "C12") (pin "2") (pinfunction "2_2") (pintype "passive"))
      (node (ref "C9") (pin "1") (pinfunction "1_1") (pintype "passive"))
      (node (ref "IC3") (pin "1") (pinfunction "DCDC_OUT_1") (pintype "passive"))
      (node (ref "IC3") (pin "3") (pinfunction "HLDO_IN_3") (pintype "passive"))
    )
    (net (code "66") (name "Net-(IC3-HLDO_OUT)") (class "Default")
      (node (ref "C15") (pin "1") (pinfunction "1_1") (pintype "passive"))
      (node (ref "C16") (pin "1") (pinfunction "1_1") (pintype "passive"))
      (node (ref "IC3") (pin "5") (pinfunction "HLDO_OUT_5") (pintype "passive"))
    )
    (net (code "67") (name "Net-(IC3-INN)") (class "Default")
      (node (ref "C17") (pin "2") (pinfunction "2_2") (pintype "passive"))
      (node (ref "IC3") (pin "7") (pinfunction "INN_7") (pintype "input"))
      (node (ref "R12") (pin "1") (pinfunction "1_1") (pintype "passive"))
    )
    (net (code "68") (name "Net-(IC3-INP)") (class "Default")
      (node (ref "C17") (pin "1") (pinfunction "1_1") (pintype "passive"))
      (node (ref "IC3") (pin "6") (pinfunction "INP_6") (pintype "input"))
      (node (ref "R10") (pin "1") (pinfunction "1_1") (pintype "passive"))
    )
    (net (code "69") (name "Net-(IC5A-S)") (class "Default")
      (node (ref "IC5") (pin "3") (pinfunction "S_3") (pintype "bidirectional"))
      (node (ref "R22") (pin "1") (pinfunction "1_1") (pintype "passive"))
      (node (ref "R23") (pin "2") (pinfunction "2_2") (pintype "passive"))
    )
    (net (code "70") (name "Net-(IC5B-S)") (class "Default")
      (node (ref "IC5") (pin "14") (pinfunction "S_14") (pintype "bidirectional"))
      (node (ref "R24") (pin "1") (pinfunction "1_1") (pintype "passive"))
      (node (ref "R25") (pin "2") (pinfunction "2_2") (pintype "passive"))
    )
    (net (code "71") (name "Net-(IC5C-S)") (class "Default")
      (node (ref "IC5") (pin "11") (pinfunction "S_11") (pintype "bidirectional"))
      (node (ref "Q2") (pin "2") (pinfunction "D_2") (pintype "passive"))
      (node (ref "Q2") (pin "4") (pinfunction "D_4") (pintype "passive"))
      (node (ref "R15") (pin "2") (pinfunction "2_2") (pintype "passive"))
    )
    (net (code "72") (name "Net-(IC5D-S)") (class "Default")
      (node (ref "IC5") (pin "6") (pinfunction "S_6") (pintype "bidirectional"))
      (node (ref "OK3") (pin "4") (pinfunction "S1_4") (pintype "passive"))
    )
    (net (code "73") (name "Net-(IC6A-+IN)") (class "Default")
      (node (ref "IC6") (pin "3") (pinfunction "+IN_3") (pintype "input"))
      (node (ref "R33") (pin "1") (pinfunction "1_1") (pintype "passive"))
    )
    (net (code "74") (name "Net-(IC6A--IN)") (class "Default")
      (node (ref "IC6") (pin "1") (pinfunction "OUT_1") (pintype "output"))
      (node (ref "IC6") (pin "4") (pinfunction "-IN_4") (pintype "input"))
      (node (ref "R34") (pin "1") (pinfunction "1_1") (pintype "passive"))
    )
    (net (code "75") (name "Net-(IC7A-D)") (class "Default")
      (node (ref "IC7") (pin "2") (pinfunction "D_2") (pintype "bidirectional"))
      (node (ref "R38") (pin "1") (pinfunction "1_1") (pintype "passive"))
      (node (ref "R39") (pin "2") (pinfunction "2_2") (pintype "passive"))
    )
    (net (code "76") (name "Net-(IC7C-D)") (class "Default")
      (node (ref "IC7") (pin "10") (pinfunction "D_10") (pintype "bidirectional"))
      (node (ref "Q4") (pin "2") (pinfunction "S_2") (pintype "passive"))
      (node (ref "R30") (pin "1") (pinfunction "1_1") (pintype "passive"))
      (node (ref "R32") (pin "2") (pinfunction "2_2") (pintype "passive"))
    )
    (net (code "77") (name "Net-(IC7D-S)") (class "Default")
      (node (ref "IC7") (pin "6") (pinfunction "S_6") (pintype "bidirectional"))
      (node (ref "R36") (pin "1") (pinfunction "1_1") (pintype "passive"))
    )
    (net (code "78") (name "Net-(IC9A-+IN)") (class "Default")
      (node (ref "C37") (pin "1") (pinfunction "1_1") (pintype "passive"))
      (node (ref "C38") (pin "1") (pinfunction "1_1") (pintype "passive"))
      (node (ref "IC9") (pin "3") (pinfunction "+IN_3") (pintype "input"))
      (node (ref "R42") (pin "1") (pinfunction "1_1") (pintype "passive"))
    )
    (net (code "79") (name "Net-(IC9A--IN)") (class "Default")
      (node (ref "C24") (pin "2") (pinfunction "2_2") (pintype "passive"))
      (node (ref "IC9") (pin "4") (pinfunction "-IN_4") (pintype "input"))
      (node (ref "R40") (pin "2") (pinfunction "2_2") (pintype "passive"))
    )
    (net (code "80") (name "Net-(IC9A-OUT)") (class "Default")
      (node (ref "C24") (pin "1") (pinfunction "1_1") (pintype "passive"))
      (node (ref "IC9") (pin "1") (pinfunction "OUT_1") (pintype "output"))
      (node (ref "R41") (pin "2") (pinfunction "2_2") (pintype "passive"))
    )
    (net (code "81") (name "Net-(IC10-VOUT)") (class "Default")
      (node (ref "C39") (pin "1") (pinfunction "1_1") (pintype "passive"))
      (node (ref "C40") (pin "+") (pinfunction "+_+") (pintype "passive"))
      (node (ref "IC10") (pin "6") (pinfunction "VOUT_6") (pintype "output"))
      (node (ref "IC8") (pin "6") (pinfunction "VOUT_S_6") (pintype "output"))
      (node (ref "IC8") (pin "7") (pinfunction "VOUT_F_7") (pintype "output"))
      (node (ref "JP7") (pin "NC") (pinfunction "NC_NC") (pintype "passive"))
      (node (ref "R42") (pin "2") (pinfunction "2_2") (pintype "passive"))
    )
    (net (code "82") (name "Net-(IC11-AVDD)") (class "Default")
      (node (ref "C54") (pin "2") (pinfunction "2_2") (pintype "passive"))
      (node (ref "C55") (pin "1") (pinfunction "1_1") (pintype "passive"))
      (node (ref "C56") (pin "1") (pinfunction "1_1") (pintype "passive"))
      (node (ref "C57") (pin "1") (pinfunction "1_1") (pintype "passive"))
      (node (ref "C58") (pin "1") (pinfunction "1_1") (pintype "passive"))
      (node (ref "C59") (pin "2") (pinfunction "2_2") (pintype "passive"))
      (node (ref "IC11") (pin "19") (pinfunction "AVDD_2_19") (pintype "power_in"))
      (node (ref "IC11") (pin "21") (pinfunction "AVDD_3_21") (pintype "power_in"))
      (node (ref "IC11") (pin "22") (pinfunction "AVDD_4_22") (pintype "power_in"))
      (node (ref "IC11") (pin "54") (pinfunction "AVDD1_54") (pintype "power_in"))
      (node (ref "IC11") (pin "56") (pinfunction "AVDD_5_56") (pintype "power_in"))
      (node (ref "IC11") (pin "59") (pinfunction "AVDD_59") (pintype "power_in"))
      (node (ref "R53") (pin "2") (pinfunction "2_2") (pintype "passive"))
    )
    (net (code "83") (name "Net-(IC11-CLK)") (class "Default")
      (node (ref "IC11") (pin "37") (pinfunction "CLK_37") (pintype "input"))
      (node (ref "JP9") (pin "2") (pinfunction "2_2") (pintype "passive"))
    )
    (net (code "84") (name "Net-(IC11-CLKSEL)") (class "Default")
      (node (ref "IC11") (pin "52") (pinfunction "CLKSEL_52") (pintype "input"))
      (node (ref "R52") (pin "1") (pinfunction "1_1") (pintype "passive"))
    )
    (net (code "85") (name "Net-(IC11-IN1N)") (class "Default")
      (node (ref "C31") (pin "2") (pinfunction "2_2") (pintype "passive"))
      (node (ref "C42") (pin "1") (pinfunction "1_1") (pintype "passive"))
      (node (ref "IC11") (pin "15") (pinfunction "IN1N_15") (pintype "input"))
      (node (ref "R44") (pin "2") (pinfunction "2_2") (pintype "passive"))
    )
    (net (code "86") (name "Net-(IC11-IN1P)") (class "Default")
      (node (ref "C32") (pin "2") (pinfunction "2_2") (pintype "passive"))
      (node (ref "C42") (pin "2") (pinfunction "2_2") (pintype "passive"))
      (node (ref "IC11") (pin "16") (pinfunction "IN1P_16") (pintype "input"))
      (node (ref "R43") (pin "2") (pinfunction "2_2") (pintype "passive"))
    )
    (net (code "87") (name "Net-(IC11-IN2N)") (class "Default")
      (node (ref "C29") (pin "2") (pinfunction "2_2") (pintype "passive"))
      (node (ref "C43") (pin "1") (pinfunction "1_1") (pintype "passive"))
      (node (ref "IC11") (pin "13") (pinfunction "IN2N_13") (pintype "input"))
      (node (ref "R46") (pin "2") (pinfunction "2_2") (pintype "passive"))
    )
    (net (code "88") (name "Net-(IC11-IN2P)") (class "Default")
      (node (ref "C30") (pin "2") (pinfunction "2_2") (pintype "passive"))
      (node (ref "C43") (pin "2") (pinfunction "2_2") (pintype "passive"))
      (node (ref "IC11") (pin "14") (pinfunction "IN2P_14") (pintype "input"))
      (node (ref "R45") (pin "2") (pinfunction "2_2") (pintype "passive"))
    )
    (net (code "89") (name "Net-(IC11-IN3N)") (class "Default")
      (node (ref "C44") (pin "1") (pinfunction "1_1") (pintype "passive"))
      (node (ref "C51") (pin "2") (pinfunction "2_2") (pintype "passive"))
      (node (ref "IC11") (pin "11") (pinfunction "IN3N_11") (pintype "input"))
      (node (ref "R48") (pin "2") (pinfunction "2_2") (pintype "passive"))
    )
    (net (code "90") (name "Net-(IC11-IN3P)") (class "Default")
      (node (ref "C44") (pin "2") (pinfunction "2_2") (pintype "passive"))
      (node (ref "C50") (pin "2") (pinfunction "2_2") (pintype "passive"))
      (node (ref "IC11") (pin "12") (pinfunction "IN3P_12") (pintype "input"))
      (node (ref "R47") (pin "2") (pinfunction "2_2") (pintype "passive"))
    )
    (net (code "91") (name "Net-(IC11-IN4N)") (class "Default")
      (node (ref "C45") (pin "1") (pinfunction "1_1") (pintype "passive"))
      (node (ref "C53") (pin "2") (pinfunction "2_2") (pintype "passive"))
      (node (ref "IC11") (pin "9") (pinfunction "IN4N_9") (pintype "input"))
      (node (ref "R50") (pin "2") (pinfunction "2_2") (pintype "passive"))
    )
    (net (code "92") (name "Net-(IC11-IN4P)") (class "Default")
      (node (ref "C45") (pin "2") (pinfunction "2_2") (pintype "passive"))
      (node (ref "C52") (pin "2") (pinfunction "2_2") (pintype "passive"))
      (node (ref "IC11") (pin "10") (pinfunction "IN4P_10") (pintype "input"))
      (node (ref "R49") (pin "2") (pinfunction "2_2") (pintype "passive"))
    )
    (net (code "93") (name "Net-(IC11-VCAP1)") (class "Default")
      (node (ref "C33") (pin "2") (pinfunction "2_2") (pintype "passive"))
      (node (ref "IC11") (pin "28") (pinfunction "VCAP1_28") (pintype "passive"))
    )
    (net (code "94") (name "Net-(IC11-VCAP2)") (class "Default")
      (node (ref "C27") (pin "2") (pinfunction "2_2") (pintype "passive"))
      (node (ref "IC11") (pin "30") (pinfunction "VCAP2_30") (pintype "passive"))
    )
    (net (code "95") (name "Net-(IC11-VCAP3)") (class "Default")
      (node (ref "C25") (pin "2") (pinfunction "2_2") (pintype "passive"))
      (node (ref "C26") (pin "1") (pinfunction "1_1") (pintype "passive"))
      (node (ref "IC11") (pin "55") (pinfunction "VCAP3_55") (pintype "passive"))
    )
    (net (code "96") (name "Net-(IC11-VCAP4)") (class "Default")
      (node (ref "C23") (pin "2") (pinfunction "2_2") (pintype "passive"))
      (node (ref "IC11") (pin "26") (pinfunction "VCAP4_26") (pintype "output"))
    )
    (net (code "97") (name "Net-(IC11-VREFP)") (class "Default")
      (node (ref "C28") (pin "1") (pinfunction "1_1") (pintype "passive"))
      (node (ref "C34") (pin "1") (pinfunction "1_1") (pintype "passive"))
      (node (ref "IC11") (pin "24") (pinfunction "VREFP_24") (pintype "bidirectional"))
      (node (ref "JP7") (pin "COM") (pinfunction "COM_COM") (pintype "passive"))
    )
    (net (code "98") (name "Net-(IC11-~{PWDN})") (class "Default")
      (node (ref "IC11") (pin "35") (pinfunction "~{PWDN}_35") (pintype "input"))
      (node (ref "R51") (pin "1") (pinfunction "1_1") (pintype "passive"))
    )
    (net (code "99") (name "Net-(IC12-EN)") (class "Default")
      (node (ref "C46") (pin "1") (pinfunction "1_1") (pintype "passive"))
      (node (ref "IC12") (pin "1") (pinfunction "IN_1") (pintype "input"))
      (node (ref "IC12") (pin "3") (pinfunction "EN_3") (pintype "input"))
      (node (ref "L4") (pin "P$1") (pinfunction "1_P$1") (pintype "passive"))
    )
    (net (code "100") (name "Net-(IC13-EN)") (class "Default")
      (node (ref "C47") (pin "1") (pinfunction "1_1") (pintype "passive"))
      (node (ref "IC13") (pin "2") (pinfunction "IN_2") (pintype "input"))
      (node (ref "IC13") (pin "3") (pinfunction "EN_3") (pintype "input"))
      (node (ref "L5") (pin "P$1") (pinfunction "1_P$1") (pintype "passive"))
    )
    (net (code "101") (name "Net-(ISEL1A_1B-COM)") (class "Default")
      (node (ref "F5") (pin "1") (pinfunction "1_1") (pintype "passive"))
      (node (ref "ISEL1A_1") (pin "4") (pinfunction "COM_4") (pintype "passive"))
      (node (ref "ISEL1A_1") (pin "9") (pinfunction "COM_9") (pintype "passive"))
    )
    (net (code "102") (name "Net-(ISEL10A_1B-COM)") (class "Default")
      (node (ref "F1") (pin "1") (pinfunction "1_1") (pintype "passive"))
      (node (ref "F2") (pin "1") (pinfunction "1_1") (pintype "passive"))
      (node (ref "ISEL10A_1") (pin "11") (pinfunction "COM_11") (pintype "passive"))
    )
    (net (code "103") (name "Net-(ISEL10A_1B-NC)") (class "Default")
      (node (ref "ISEL10A_1") (pin "12") (pinfunction "NC_12") (pintype "passive"))
      (node (ref "R11") (pin "2") (pinfunction "2_2") (pintype "passive"))
      (node (ref "R8") (pin "1") (pinfunction "1_1") (pintype "passive"))
    )
    (net (code "104") (name "Net-(ISEL10A_1C-COM)") (class "Default")
      (node (ref "ISEL10A_1") (pin "21") (pinfunction "COM_21") (pintype "passive"))
      (node (ref "L2") (pin "4") (pinfunction "4_4") (pintype "passive"))
    )
    (net (code "105") (name "Net-(ISEL10A_1C-NC)") (class "Default")
      (node (ref "ISEL10A_1") (pin "22") (pinfunction "NC_22") (pintype "passive"))
      (node (ref "R11") (pin "2S") (pinfunction "2S_2S") (pintype "passive"))
    )
    (net (code "106") (name "Net-(ISEL10A_1C-NO)") (class "Default")
      (node (ref "F2") (pin "2") (pinfunction "2_2") (pintype "passive"))
      (node (ref "ISEL10A_1") (pin "24") (pinfunction "NO_24") (pintype "passive"))
      (node (ref "R8") (pin "2") (pinfunction "2_2") (pintype "passive"))
    )
    (net (code "107") (name "Net-(ISEL10A_2B-COM)") (class "Default")
      (node (ref "F4") (pin "1") (pinfunction "1_1") (pintype "passive"))
      (node (ref "ISEL10A_2") (pin "11") (pinfunction "COM_11") (pintype "passive"))
      (node (ref "ISEL10A_2") (pin "21") (pinfunction "COM_21") (pintype "passive"))
    )
    (net (code "108") (name "Net-(ISEL10A_2B-NC)") (class "Default")
      (node (ref "ISEL10A_2") (pin "12") (pinfunction "NC_12") (pintype "passive"))
      (node (ref "ISEL10A_2") (pin "22") (pinfunction "NC_22") (pintype "passive"))
      (node (ref "R32") (pin "1") (pinfunction "1_1") (pintype "passive"))
      (node (ref "R35") (pin "2") (pinfunction "2_2") (pintype "passive"))
      (node (ref "R35") (pin "2S") (pinfunction "2S_2S") (pintype "passive"))
    )
    (net (code "109") (name "Net-(ISEL10A_2B-NO)") (class "Default")
      (node (ref "F5") (pin "2") (pinfunction "2_2") (pintype "passive"))
      (node (ref "ISEL10A_2") (pin "14") (pinfunction "NO_14") (pintype "passive"))
      (node (ref "ISEL10A_2") (pin "24") (pinfunction "NO_24") (pintype "passive"))
    )
    (net (code "110") (name "Net-(JP7-PadNO)") (class "Default")
      (node (ref "JP7") (pin "NO") (pinfunction "NO_NO") (pintype "passive"))
      (node (ref "R40") (pin "1") (pinfunction "1_1") (pintype "passive"))
      (node (ref "R41") (pin "1") (pinfunction "1_1") (pintype "passive"))
    )
    (net (code "111") (name "Net-(JP8-PadCOM)") (class "Default")
      (node (ref "JP8") (pin "COM") (pinfunction "COM_COM") (pintype "passive"))
      (node (ref "R52") (pin "2") (pinfunction "2_2") (pintype "passive"))
    )
    (net (code "112") (name "Net-(L1-1)") (class "Default")
      (node (ref "L1") (pin "P$1") (pinfunction "1_P$1") (pintype "passive"))
      (node (ref "R1") (pin "2") (pinfunction "2_2") (pintype "passive"))
    )
    (net (code "113") (name "Net-(L2-Pad1)") (class "Default")
      (node (ref "L2") (pin "1") (pinfunction "1_1") (pintype "passive"))
      (node (ref "R11") (pin "1S") (pinfunction "1S_1S") (pintype "passive"))
    )
    (net (code "114") (name "Net-(L2-Pad3)") (class "Default")
      (node (ref "L2") (pin "3") (pinfunction "3_3") (pintype "passive"))
      (node (ref "R10") (pin "2") (pinfunction "2_2") (pintype "passive"))
    )
    (net (code "115") (name "Net-(L3-2)") (class "Default")
      (node (ref "L3") (pin "P$2") (pinfunction "2_P$2") (pintype "passive"))
      (node (ref "X1") (pin "5") (pinfunction "1_5") (pintype "passive"))
    )
    (net (code "116") (name "Net-(OK1-A)") (class "Default")
      (node (ref "OK1") (pin "1") (pinfunction "A_1") (pintype "passive"))
      (node (ref "R2") (pin "1") (pinfunction "1_1") (pintype "passive"))
    )
    (net (code "117") (name "Net-(OK1-S2)") (class "Default")
      (node (ref "OK1") (pin "3") (pinfunction "S2_3") (pintype "passive"))
      (node (ref "R6") (pin "2") (pinfunction "2_2") (pintype "passive"))
    )
    (net (code "118") (name "Net-(OK2-A)") (class "Default")
      (node (ref "OK2") (pin "1") (pinfunction "A_1") (pintype "passive"))
      (node (ref "R14") (pin "1") (pinfunction "1_1") (pintype "passive"))
    )
    (net (code "119") (name "Net-(OK3-A)") (class "Default")
      (node (ref "OK3") (pin "1") (pinfunction "A_1") (pintype "passive"))
      (node (ref "R16") (pin "2") (pinfunction "2_2") (pintype "passive"))
    )
    (net (code "120") (name "Net-(OK3-S2)") (class "Default")
      (node (ref "OK3") (pin "3") (pinfunction "S2_3") (pintype "passive"))
      (node (ref "R18") (pin "1") (pinfunction "1_1") (pintype "passive"))
    )
    (net (code "121") (name "Net-(Q1-S)") (class "Default")
      (node (ref "Q1") (pin "3") (pinfunction "S_3") (pintype "passive"))
      (node (ref "Q2") (pin "1") (pinfunction "G_1") (pintype "passive"))
      (node (ref "R13") (pin "2") (pinfunction "2_2") (pintype "passive"))
    )
    (net (code "122") (name "Net-(Q3-D)") (class "Default")
      (node (ref "Q3") (pin "3") (pinfunction "D_3") (pintype "passive"))
      (node (ref "Q4") (pin "3") (pinfunction "D_3") (pintype "passive"))
    )
    (net (code "123") (name "Net-(R1-Pad1)") (class "Default")
      (node (ref "R1") (pin "1") (pinfunction "1_1") (pintype "passive"))
      (node (ref "R3") (pin "2") (pinfunction "2_2") (pintype "passive"))
    )
    (net (code "124") (name "Net-(R3-Pad1)") (class "Default")
      (node (ref "R3") (pin "1") (pinfunction "1_1") (pintype "passive"))
      (node (ref "R5") (pin "2") (pinfunction "2_2") (pintype "passive"))
    )
    (net (code "125") (name "Net-(R17-Pad1)") (class "Default")
      (node (ref "R17") (pin "1") (pinfunction "1_1") (pintype "passive"))
      (node (ref "R18") (pin "2") (pinfunction "2_2") (pintype "passive"))
    )
    (net (code "126") (name "Net-(R20-Pad1)") (class "Default")
      (node (ref "R20") (pin "1") (pinfunction "1_1") (pintype "passive"))
      (node (ref "R21") (pin "2") (pinfunction "2_2") (pintype "passive"))
    )
    (net (code "127") (name "Net-(R21-Pad1)") (class "Default")
      (node (ref "R21") (pin "1") (pinfunction "1_1") (pintype "passive"))
      (node (ref "R22") (pin "2") (pinfunction "2_2") (pintype "passive"))
    )
    (net (code "128") (name "Net-(R23-Pad1)") (class "Default")
      (node (ref "R23") (pin "1") (pinfunction "1_1") (pintype "passive"))
      (node (ref "R24") (pin "2") (pinfunction "2_2") (pintype "passive"))
    )
    (net (code "129") (name "Net-(R37-Pad1)") (class "Default")
      (node (ref "R37") (pin "1") (pinfunction "1_1") (pintype "passive"))
      (node (ref "R38") (pin "2") (pinfunction "2_2") (pintype "passive"))
    )
    (net (code "130") (name "Net-(X1C-1)") (class "Default")
      (node (ref "F1") (pin "2") (pinfunction "2_2") (pintype "passive"))
      (node (ref "X1") (pin "3") (pinfunction "1_3") (pintype "passive"))
    )
    (net (code "131") (name "Net-(X1D-1)") (class "Default")
      (node (ref "R11") (pin "1") (pinfunction "1_1") (pintype "passive"))
      (node (ref "X1") (pin "4") (pinfunction "1_4") (pintype "passive"))
    )
    (net (code "132") (name "Net-(X2P-1)") (class "Default")
      (node (ref "JP1") (pin "2") (pinfunction "2_2") (pintype "passive"))
      (node (ref "X2") (pin "23") (pinfunction "1_23") (pintype "passive"))
    )
    (net (code "133") (name "Net-(X2Q-1)") (class "Default")
      (node (ref "JP2") (pin "1") (pinfunction "1_1") (pintype "passive"))
      (node (ref "X2") (pin "24") (pinfunction "1_24") (pintype "passive"))
    )
    (net (code "134") (name "Net-(X2R-1)") (class "Default")
      (node (ref "JP3") (pin "2") (pinfunction "2_2") (pintype "passive"))
      (node (ref "X2") (pin "25") (pinfunction "1_25") (pintype "passive"))
    )
    (net (code "135") (name "Net-(X2S-1)") (class "Default")
      (node (ref "JP4") (pin "1") (pinfunction "1_1") (pintype "passive"))
      (node (ref "X2") (pin "26") (pinfunction "1_26") (pintype "passive"))
    )
    (net (code "136") (name "USEL#1") (class "Default")
      (node (ref "R2") (pin "2") (pinfunction "2_2") (pintype "passive"))
      (node (ref "X3") (pin "5") (pinfunction "1_5") (pintype "passive"))
    )
    (net (code "137") (name "USEL1#3") (class "Default")
      (node (ref "IC5") (pin "8") (pinfunction "IN_8") (pintype "input"))
      (node (ref "R16") (pin "1") (pinfunction "1_1") (pintype "passive"))
      (node (ref "X3") (pin "11") (pinfunction "1_11") (pintype "passive"))
    )
    (net (code "138") (name "USEL1#4") (class "Default")
      (node (ref "IC7") (pin "8") (pinfunction "IN_8") (pintype "input"))
      (node (ref "X3") (pin "12") (pinfunction "1_12") (pintype "passive"))
    )
    (net (code "139") (name "USEL5#4") (class "Default")
      (node (ref "IC7") (pin "1") (pinfunction "IN_1") (pintype "input"))
      (node (ref "X3") (pin "14") (pinfunction "1_14") (pintype "passive"))
    )
    (net (code "140") (name "USEL20#3") (class "Default")
      (node (ref "IC5") (pin "1") (pinfunction "IN_1") (pintype "input"))
      (node (ref "X3") (pin "13") (pinfunction "1_13") (pintype "passive"))
    )
    (net (code "141") (name "USEL100#3") (class "Default")
      (node (ref "IC5") (pin "16") (pinfunction "IN_16") (pintype "input"))
      (node (ref "X3") (pin "9") (pinfunction "1_9") (pintype "passive"))
    )
    (net (code "142") (name "unconnected-(IC2-1B-Pad1)") (class "Default")
      (node (ref "IC2") (pin "1") (pinfunction "1B_1") (pintype "input"))
    )
    (net (code "143") (name "unconnected-(IC2-1C-Pad18)") (class "Default")
      (node (ref "IC2") (pin "18") (pinfunction "1C_18") (pintype "output"))
    )
    (net (code "144") (name "unconnected-(IC2-2B-Pad2)") (class "Default")
      (node (ref "IC2") (pin "2") (pinfunction "2B_2") (pintype "input"))
    )
    (net (code "145") (name "unconnected-(IC2-2C-Pad17)") (class "Default")
      (node (ref "IC2") (pin "17") (pinfunction "2C_17") (pintype "output"))
    )
    (net (code "146") (name "unconnected-(IC10-TEMP-Pad3)") (class "Default")
      (node (ref "IC10") (pin "3") (pinfunction "TEMP_3") (pintype "input"))
    )
    (net (code "147") (name "unconnected-(IC10-TRIM{slash}NR-Pad5)") (class "Default")
      (node (ref "IC10") (pin "5") (pinfunction "TRIM/NR_5") (pintype "input"))
    )
    (net (code "148") (name "unconnected-(IC11-GPIO1-Pad42)") (class "Default")
      (node (ref "IC11") (pin "42") (pinfunction "GPIO1_42") (pintype "bidirectional"))
    )
    (net (code "149") (name "unconnected-(IC11-GPIO2-Pad44)") (class "Default")
      (node (ref "IC11") (pin "44") (pinfunction "GPIO2_44") (pintype "bidirectional"))
    )
    (net (code "150") (name "unconnected-(IC11-GPIO3-Pad45)") (class "Default")
      (node (ref "IC11") (pin "45") (pinfunction "GPIO3_45") (pintype "bidirectional"))
    )
    (net (code "151") (name "unconnected-(IC11-GPIO4-Pad46)") (class "Default")
      (node (ref "IC11") (pin "46") (pinfunction "GPIO4_46") (pintype "bidirectional"))
    )
    (net (code "152") (name "unconnected-(IC11-IN5N(NC)-Pad7)") (class "Default")
      (node (ref "IC11") (pin "7") (pinfunction "IN5N(NC)_7") (pintype "input"))
    )
    (net (code "153") (name "unconnected-(IC11-IN5P(NC)-Pad8)") (class "Default")
      (node (ref "IC11") (pin "8") (pinfunction "IN5P(NC)_8") (pintype "input"))
    )
    (net (code "154") (name "unconnected-(IC11-IN6N(NC)-Pad5)") (class "Default")
      (node (ref "IC11") (pin "5") (pinfunction "IN6N(NC)_5") (pintype "input"))
    )
    (net (code "155") (name "unconnected-(IC11-IN6P(NC)-Pad6)") (class "Default")
      (node (ref "IC11") (pin "6") (pinfunction "IN6P(NC)_6") (pintype "input"))
    )
    (net (code "156") (name "unconnected-(IC11-IN7N(NC)-Pad3)") (class "Default")
      (node (ref "IC11") (pin "3") (pinfunction "IN7N(NC)_3") (pintype "input"))
    )
    (net (code "157") (name "unconnected-(IC11-IN7P(NC)-Pad4)") (class "Default")
      (node (ref "IC11") (pin "4") (pinfunction "IN7P(NC)_4") (pintype "input"))
    )
    (net (code "158") (name "unconnected-(IC11-IN8N(NC)-Pad1)") (class "Default")
      (node (ref "IC11") (pin "1") (pinfunction "IN8N(NC)_1") (pintype "input"))
    )
    (net (code "159") (name "unconnected-(IC11-IN8P(NC)-Pad2)") (class "Default")
      (node (ref "IC11") (pin "2") (pinfunction "IN8P(NC)_2") (pintype "input"))
    )
    (net (code "160") (name "unconnected-(IC11-OPAMPN-Pad61)") (class "Default")
      (node (ref "IC11") (pin "61") (pinfunction "OPAMPN_61") (pintype "input"))
    )
    (net (code "161") (name "unconnected-(IC11-OPAMPOUT-Pad63)") (class "Default")
      (node (ref "IC11") (pin "63") (pinfunction "OPAMPOUT_63") (pintype "output"))
    )
    (net (code "162") (name "unconnected-(IC11-OPAMPP-Pad60)") (class "Default")
      (node (ref "IC11") (pin "60") (pinfunction "OPAMPP_60") (pintype "input"))
    )
    (net (code "163") (name "unconnected-(IC11-TESTN-Pad18)") (class "Default")
      (node (ref "IC11") (pin "18") (pinfunction "TESTN_18") (pintype "bidirectional"))
    )
    (net (code "164") (name "unconnected-(IC11-TESTP-Pad17)") (class "Default")
      (node (ref "IC11") (pin "17") (pinfunction "TESTP_17") (pintype "bidirectional"))
    )
    (net (code "165") (name "unconnected-(IC12-NR-Pad4)") (class "Default")
      (node (ref "IC12") (pin "4") (pinfunction "NR_4") (pintype "passive"))
    )
    (net (code "166") (name "unconnected-(IC13-NR-Pad4)") (class "Default")
      (node (ref "IC13") (pin "4") (pinfunction "NR_4") (pintype "passive"))
    )
    (net (code "167") (name "unconnected-(ISEL10A_1B-NO-Pad14)") (class "Default")
      (node (ref "ISEL10A_1") (pin "14") (pinfunction "NO_14") (pintype "passive"))
    )
    (net (code "168") (name "unconnected-(X2I-1-Pad17)") (class "Default")
      (node (ref "X2") (pin "17") (pinfunction "1_17") (pintype "passive"))
    )
    (net (code "169") (name "unconnected-(X2J-1-Pad18)") (class "Default")
      (node (ref "X2") (pin "18") (pinfunction "1_18") (pintype "passive"))
    )
    (net (code "170") (name "unconnected-(X3B-1-Pad10)") (class "Default")
      (node (ref "X3") (pin "10") (pinfunction "1_10") (pintype "passive"))
    )
    (net (code "171") (name "unconnected-(X3G-1-Pad15)") (class "Default")
      (node (ref "X3") (pin "15") (pinfunction "1_15") (pintype "passive"))
    )
    (net (code "172") (name "unconnected-(X3I-1-Pad17)") (class "Default")
      (node (ref "X3") (pin "17") (pinfunction "1_17") (pintype "passive"))
    )
    (net (code "173") (name "unconnected-(X3K-1-Pad19)") (class "Default")
      (node (ref "X3") (pin "19") (pinfunction "1_19") (pintype "passive"))
    )
    (net (code "174") (name "unconnected-(X3L-1-Pad2)") (class "Default")
      (node (ref "X3") (pin "2") (pinfunction "1_2") (pintype "passive"))
    )
    (net (code "175") (name "unconnected-(X3N-1-Pad21)") (class "Default")
      (node (ref "X3") (pin "21") (pinfunction "1_21") (pintype "passive"))
    )
    (net (code "176") (name "unconnected-(X3R-1-Pad25)") (class "Default")
      (node (ref "X3") (pin "25") (pinfunction "1_25") (pintype "passive"))
    )
    (net (code "177") (name "unconnected-(X3S-1-Pad26)") (class "Default")
      (node (ref "X3") (pin "26") (pinfunction "1_26") (pintype "passive"))
    )
    (net (code "178") (name "unconnected-(X3Z-1-Pad7)") (class "Default")
      (node (ref "X3") (pin "7") (pinfunction "1_7") (pintype "passive"))
    )
    (net (code "179") (name "~{ADC_CS}") (class "Default")
      (node (ref "IC11") (pin "39") (pinfunction "~{CS}_39") (pintype "input"))
      (node (ref "X2") (pin "5") (pinfunction "1_5") (pintype "passive"))
    )
    (net (code "180") (name "~{ADC_DRDY}") (class "Default")
      (node (ref "IC11") (pin "47") (pinfunction "~{DRDY}_47") (pintype "output"))
      (node (ref "X2") (pin "7") (pinfunction "1_7") (pintype "passive"))
    )
    (net (code "181") (name "~{RESET}") (class "Default")
      (node (ref "IC11") (pin "36") (pinfunction "~{RESET}_36") (pintype "input"))
      (node (ref "X2") (pin "9") (pinfunction "1_9") (pintype "passive"))
    )
  )
)
